# DAC.net
KiCad netlist of a schematic drawn in Altium Designer
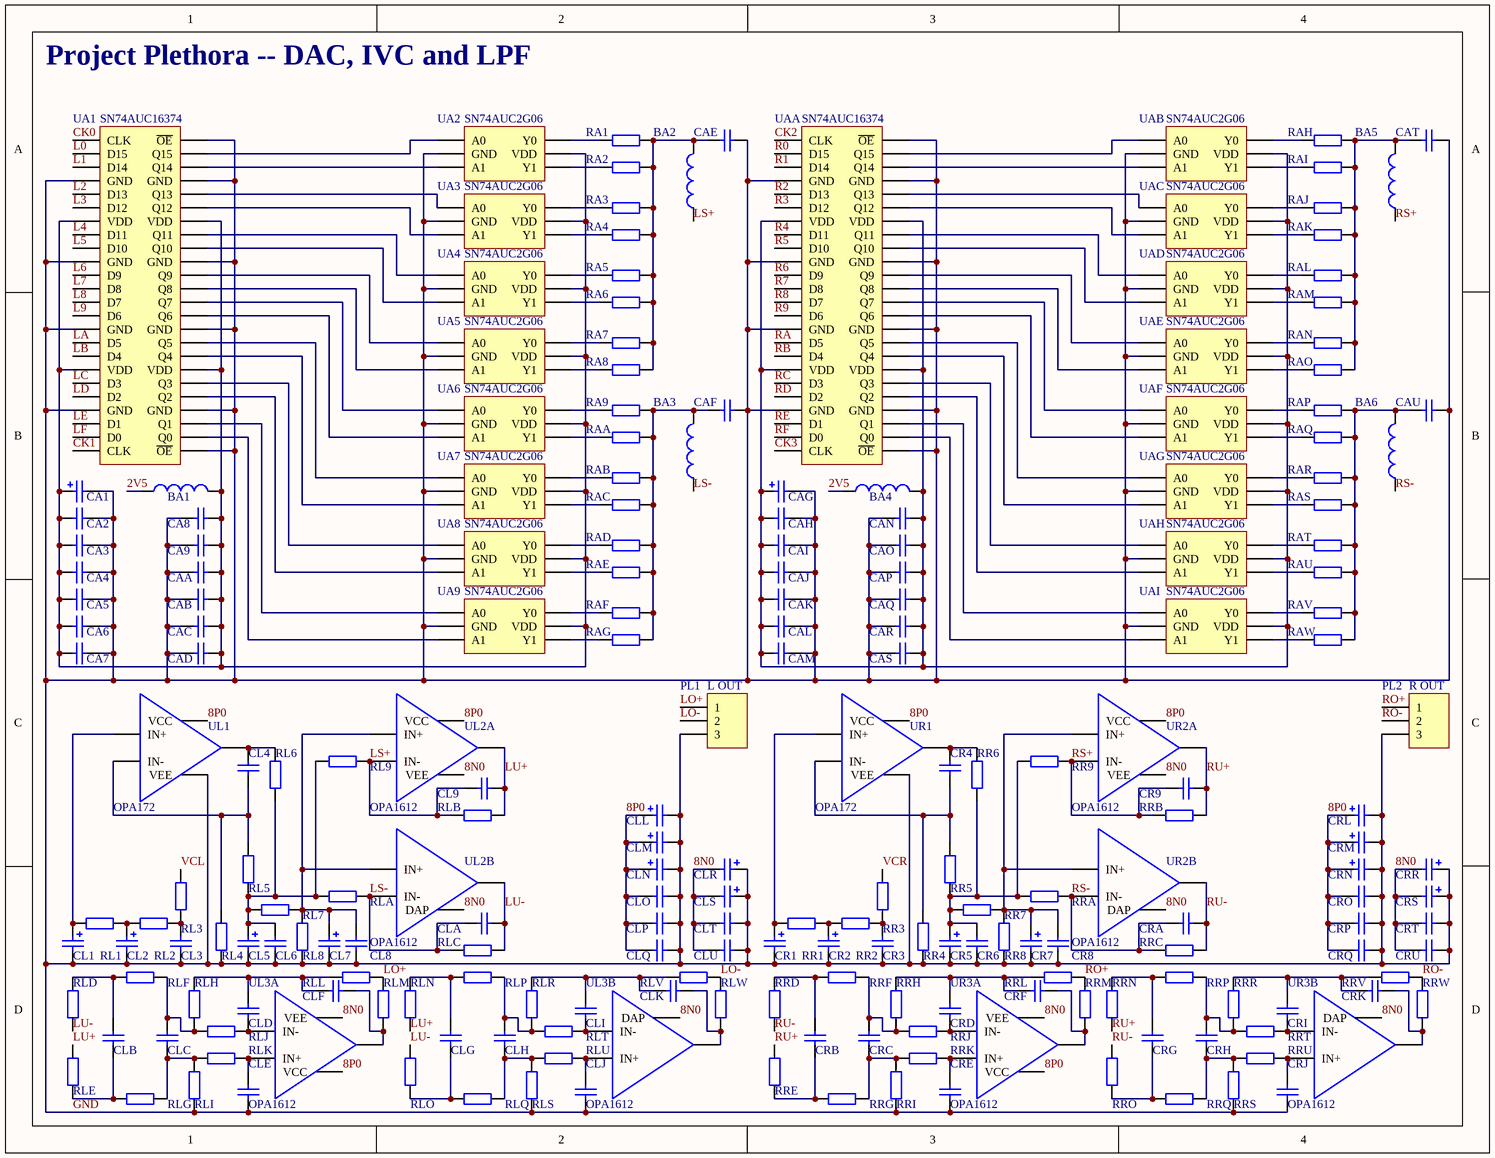
[diagram p0: DAC.SchDoc]

(export (version "E")
  (design (tool "Eeschema 10.0.6"))
  (components
    (comp (ref "BA1")
      (value "Inductor")
      (footprint "0402")
      (fields (field (name "PUBLISHER") "Altium Limited"))
      (libsource (lib "Miscellaneous Devices") (part "Inductor"))
    )
    (comp (ref "BA2")
      (value "Inductor")
      (footprint "0402")
      (fields (field (name "PUBLISHER") "Altium Limited"))
      (libsource (lib "Miscellaneous Devices") (part "Inductor"))
    )
    (comp (ref "BA3")
      (value "Inductor")
      (footprint "0402")
      (fields (field (name "PUBLISHER") "Altium Limited"))
      (libsource (lib "Miscellaneous Devices") (part "Inductor"))
    )
    (comp (ref "BA4")
      (value "Inductor")
      (footprint "0402")
      (fields (field (name "PUBLISHER") "Altium Limited"))
      (libsource (lib "Miscellaneous Devices") (part "Inductor"))
    )
    (comp (ref "BA5")
      (value "Inductor")
      (footprint "0402")
      (fields (field (name "PUBLISHER") "Altium Limited"))
      (libsource (lib "Miscellaneous Devices") (part "Inductor"))
    )
    (comp (ref "BA6")
      (value "Inductor")
      (footprint "0402")
      (fields (field (name "PUBLISHER") "Altium Limited"))
      (libsource (lib "Miscellaneous Devices") (part "Inductor"))
    )
    (comp (ref "CA1")
      (value "Cap Pol2")
      (footprint "0603")
      (description "Polarized Capacitor (Axial)")
      (fields (field (name "PUBLISHER") "Altium Limited"))
      (libsource (lib "Miscellaneous Devices") (part "Cap Pol2"))
    )
    (comp (ref "CA2")
      (value "Cap")
      (footprint "0402")
      (description "Capacitor")
      (fields (field (name "PUBLISHER") "Altium Limited"))
      (libsource (lib "Miscellaneous Devices") (part "Cap"))
    )
    (comp (ref "CA3")
      (value "Cap")
      (footprint "0402")
      (description "Capacitor")
      (fields (field (name "PUBLISHER") "Altium Limited"))
      (libsource (lib "Miscellaneous Devices") (part "Cap"))
    )
    (comp (ref "CA4")
      (value "Cap")
      (footprint "0402")
      (description "Capacitor")
      (fields (field (name "PUBLISHER") "Altium Limited"))
      (libsource (lib "Miscellaneous Devices") (part "Cap"))
    )
    (comp (ref "CA5")
      (value "Cap")
      (footprint "0402")
      (description "Capacitor")
      (fields (field (name "PUBLISHER") "Altium Limited"))
      (libsource (lib "Miscellaneous Devices") (part "Cap"))
    )
    (comp (ref "CA6")
      (value "Cap")
      (footprint "0402")
      (description "Capacitor")
      (fields (field (name "PUBLISHER") "Altium Limited"))
      (libsource (lib "Miscellaneous Devices") (part "Cap"))
    )
    (comp (ref "CA7")
      (value "Cap")
      (footprint "0402")
      (description "Capacitor")
      (fields (field (name "PUBLISHER") "Altium Limited"))
      (libsource (lib "Miscellaneous Devices") (part "Cap"))
    )
    (comp (ref "CA8")
      (value "Cap")
      (footprint "0402")
      (description "Capacitor")
      (fields (field (name "PUBLISHER") "Altium Limited"))
      (libsource (lib "Miscellaneous Devices") (part "Cap"))
    )
    (comp (ref "CA9")
      (value "Cap")
      (footprint "0402")
      (description "Capacitor")
      (fields (field (name "PUBLISHER") "Altium Limited"))
      (libsource (lib "Miscellaneous Devices") (part "Cap"))
    )
    (comp (ref "CAA")
      (value "Cap")
      (footprint "0402")
      (description "Capacitor")
      (fields (field (name "PUBLISHER") "Altium Limited"))
      (libsource (lib "Miscellaneous Devices") (part "Cap"))
    )
    (comp (ref "CAB")
      (value "Cap")
      (footprint "0402")
      (description "Capacitor")
      (fields (field (name "PUBLISHER") "Altium Limited"))
      (libsource (lib "Miscellaneous Devices") (part "Cap"))
    )
    (comp (ref "CAC")
      (value "Cap")
      (footprint "0402")
      (description "Capacitor")
      (fields (field (name "PUBLISHER") "Altium Limited"))
      (libsource (lib "Miscellaneous Devices") (part "Cap"))
    )
    (comp (ref "CAD")
      (value "Cap")
      (footprint "0402")
      (description "Capacitor")
      (fields (field (name "PUBLISHER") "Altium Limited"))
      (libsource (lib "Miscellaneous Devices") (part "Cap"))
    )
    (comp (ref "CAE")
      (value "Cap")
      (footprint "0402")
      (description "Capacitor")
      (fields (field (name "PUBLISHER") "Altium Limited"))
      (libsource (lib "Miscellaneous Devices") (part "Cap"))
    )
    (comp (ref "CAF")
      (value "Cap")
      (footprint "0402")
      (description "Capacitor")
      (fields (field (name "PUBLISHER") "Altium Limited"))
      (libsource (lib "Miscellaneous Devices") (part "Cap"))
    )
    (comp (ref "CAG")
      (value "Cap Pol2")
      (footprint "0603")
      (description "Polarized Capacitor (Axial)")
      (fields (field (name "PUBLISHER") "Altium Limited"))
      (libsource (lib "Miscellaneous Devices") (part "Cap Pol2"))
    )
    (comp (ref "CAH")
      (value "Cap")
      (footprint "0402")
      (description "Capacitor")
      (fields (field (name "PUBLISHER") "Altium Limited"))
      (libsource (lib "Miscellaneous Devices") (part "Cap"))
    )
    (comp (ref "CAI")
      (value "Cap")
      (footprint "0402")
      (description "Capacitor")
      (fields (field (name "PUBLISHER") "Altium Limited"))
      (libsource (lib "Miscellaneous Devices") (part "Cap"))
    )
    (comp (ref "CAJ")
      (value "Cap")
      (footprint "0402")
      (description "Capacitor")
      (fields (field (name "PUBLISHER") "Altium Limited"))
      (libsource (lib "Miscellaneous Devices") (part "Cap"))
    )
    (comp (ref "CAK")
      (value "Cap")
      (footprint "0402")
      (description "Capacitor")
      (fields (field (name "PUBLISHER") "Altium Limited"))
      (libsource (lib "Miscellaneous Devices") (part "Cap"))
    )
    (comp (ref "CAL")
      (value "Cap")
      (footprint "0402")
      (description "Capacitor")
      (fields (field (name "PUBLISHER") "Altium Limited"))
      (libsource (lib "Miscellaneous Devices") (part "Cap"))
    )
    (comp (ref "CAM")
      (value "Cap")
      (footprint "0402")
      (description "Capacitor")
      (fields (field (name "PUBLISHER") "Altium Limited"))
      (libsource (lib "Miscellaneous Devices") (part "Cap"))
    )
    (comp (ref "CAN")
      (value "Cap")
      (footprint "0402")
      (description "Capacitor")
      (fields (field (name "PUBLISHER") "Altium Limited"))
      (libsource (lib "Miscellaneous Devices") (part "Cap"))
    )
    (comp (ref "CAO")
      (value "Cap")
      (footprint "0402")
      (description "Capacitor")
      (fields (field (name "PUBLISHER") "Altium Limited"))
      (libsource (lib "Miscellaneous Devices") (part "Cap"))
    )
    (comp (ref "CAP")
      (value "Cap")
      (footprint "0402")
      (description "Capacitor")
      (fields (field (name "PUBLISHER") "Altium Limited"))
      (libsource (lib "Miscellaneous Devices") (part "Cap"))
    )
    (comp (ref "CAQ")
      (value "Cap")
      (footprint "0402")
      (description "Capacitor")
      (fields (field (name "PUBLISHER") "Altium Limited"))
      (libsource (lib "Miscellaneous Devices") (part "Cap"))
    )
    (comp (ref "CAR")
      (value "Cap")
      (footprint "0402")
      (description "Capacitor")
      (fields (field (name "PUBLISHER") "Altium Limited"))
      (libsource (lib "Miscellaneous Devices") (part "Cap"))
    )
    (comp (ref "CAS")
      (value "Cap")
      (footprint "0402")
      (description "Capacitor")
      (fields (field (name "PUBLISHER") "Altium Limited"))
      (libsource (lib "Miscellaneous Devices") (part "Cap"))
    )
    (comp (ref "CAT")
      (value "Cap")
      (footprint "0402")
      (description "Capacitor")
      (fields (field (name "PUBLISHER") "Altium Limited"))
      (libsource (lib "Miscellaneous Devices") (part "Cap"))
    )
    (comp (ref "CAU")
      (value "Cap")
      (footprint "0402")
      (description "Capacitor")
      (fields (field (name "PUBLISHER") "Altium Limited"))
      (libsource (lib "Miscellaneous Devices") (part "Cap"))
    )
    (comp (ref "CL1")
      (value "Cap Pol2")
      (footprint "0603")
      (description "Polarized Capacitor (Axial)")
      (fields (field (name "PUBLISHER") "Altium Limited"))
      (libsource (lib "Miscellaneous Devices") (part "Cap Pol2"))
    )
    (comp (ref "CL2")
      (value "Cap Pol2")
      (footprint "0603")
      (description "Polarized Capacitor (Axial)")
      (fields (field (name "PUBLISHER") "Altium Limited"))
      (libsource (lib "Miscellaneous Devices") (part "Cap Pol2"))
    )
    (comp (ref "CL3")
      (value "Cap")
      (footprint "0603")
      (description "Capacitor")
      (fields (field (name "PUBLISHER") "Altium Limited"))
      (libsource (lib "Miscellaneous Devices") (part "Cap"))
    )
    (comp (ref "CL4")
      (value "Cap")
      (footprint "0603")
      (description "Capacitor")
      (fields (field (name "PUBLISHER") "Altium Limited"))
      (libsource (lib "Miscellaneous Devices") (part "Cap"))
    )
    (comp (ref "CL5")
      (value "Cap Pol2")
      (footprint "0603")
      (description "Polarized Capacitor (Axial)")
      (fields (field (name "PUBLISHER") "Altium Limited"))
      (libsource (lib "Miscellaneous Devices") (part "Cap Pol2"))
    )
    (comp (ref "CL6")
      (value "Cap")
      (footprint "0603")
      (description "Capacitor")
      (fields (field (name "PUBLISHER") "Altium Limited"))
      (libsource (lib "Miscellaneous Devices") (part "Cap"))
    )
    (comp (ref "CL7")
      (value "Cap Pol2")
      (footprint "0603")
      (description "Polarized Capacitor (Axial)")
      (fields (field (name "PUBLISHER") "Altium Limited"))
      (libsource (lib "Miscellaneous Devices") (part "Cap Pol2"))
    )
    (comp (ref "CL8")
      (value "Cap")
      (footprint "0603")
      (description "Capacitor")
      (fields (field (name "PUBLISHER") "Altium Limited"))
      (libsource (lib "Miscellaneous Devices") (part "Cap"))
    )
    (comp (ref "CL9")
      (value "Cap")
      (footprint "0603")
      (description "Capacitor")
      (fields (field (name "PUBLISHER") "Altium Limited"))
      (libsource (lib "Miscellaneous Devices") (part "Cap"))
    )
    (comp (ref "CLA")
      (value "Cap")
      (footprint "0603")
      (description "Capacitor")
      (fields (field (name "PUBLISHER") "Altium Limited"))
      (libsource (lib "Miscellaneous Devices") (part "Cap"))
    )
    (comp (ref "CLB")
      (value "Cap")
      (footprint "0603")
      (description "Capacitor")
      (fields (field (name "PUBLISHER") "Altium Limited"))
      (libsource (lib "Miscellaneous Devices") (part "Cap"))
    )
    (comp (ref "CLC")
      (value "Cap")
      (footprint "0603")
      (description "Capacitor")
      (fields (field (name "PUBLISHER") "Altium Limited"))
      (libsource (lib "Miscellaneous Devices") (part "Cap"))
    )
    (comp (ref "CLD")
      (value "Cap")
      (footprint "0603")
      (description "Capacitor")
      (fields (field (name "PUBLISHER") "Altium Limited"))
      (libsource (lib "Miscellaneous Devices") (part "Cap"))
    )
    (comp (ref "CLE")
      (value "Cap")
      (footprint "0603")
      (description "Capacitor")
      (fields (field (name "PUBLISHER") "Altium Limited"))
      (libsource (lib "Miscellaneous Devices") (part "Cap"))
    )
    (comp (ref "CLF")
      (value "Cap")
      (footprint "0603")
      (description "Capacitor")
      (fields (field (name "PUBLISHER") "Altium Limited"))
      (libsource (lib "Miscellaneous Devices") (part "Cap"))
    )
    (comp (ref "CLG")
      (value "Cap")
      (footprint "0603")
      (description "Capacitor")
      (fields (field (name "PUBLISHER") "Altium Limited"))
      (libsource (lib "Miscellaneous Devices") (part "Cap"))
    )
    (comp (ref "CLH")
      (value "Cap")
      (footprint "0603")
      (description "Capacitor")
      (fields (field (name "PUBLISHER") "Altium Limited"))
      (libsource (lib "Miscellaneous Devices") (part "Cap"))
    )
    (comp (ref "CLI")
      (value "Cap")
      (footprint "0603")
      (description "Capacitor")
      (fields (field (name "PUBLISHER") "Altium Limited"))
      (libsource (lib "Miscellaneous Devices") (part "Cap"))
    )
    (comp (ref "CLJ")
      (value "Cap")
      (footprint "0603")
      (description "Capacitor")
      (fields (field (name "PUBLISHER") "Altium Limited"))
      (libsource (lib "Miscellaneous Devices") (part "Cap"))
    )
    (comp (ref "CLK")
      (value "Cap")
      (footprint "0603")
      (description "Capacitor")
      (fields (field (name "PUBLISHER") "Altium Limited"))
      (libsource (lib "Miscellaneous Devices") (part "Cap"))
    )
    (comp (ref "CLL")
      (value "Cap Pol2")
      (footprint "0603")
      (description "Polarized Capacitor (Axial)")
      (fields (field (name "PUBLISHER") "Altium Limited"))
      (libsource (lib "Miscellaneous Devices") (part "Cap Pol2"))
    )
    (comp (ref "CLM")
      (value "Cap Pol2")
      (footprint "0603")
      (description "Polarized Capacitor (Axial)")
      (fields (field (name "PUBLISHER") "Altium Limited"))
      (libsource (lib "Miscellaneous Devices") (part "Cap Pol2"))
    )
    (comp (ref "CLN")
      (value "Cap Pol2")
      (footprint "0603")
      (description "Polarized Capacitor (Axial)")
      (fields (field (name "PUBLISHER") "Altium Limited"))
      (libsource (lib "Miscellaneous Devices") (part "Cap Pol2"))
    )
    (comp (ref "CLO")
      (value "Cap")
      (footprint "0603")
      (description "Capacitor")
      (fields (field (name "PUBLISHER") "Altium Limited"))
      (libsource (lib "Miscellaneous Devices") (part "Cap"))
    )
    (comp (ref "CLP")
      (value "Cap")
      (footprint "0603")
      (description "Capacitor")
      (fields (field (name "PUBLISHER") "Altium Limited"))
      (libsource (lib "Miscellaneous Devices") (part "Cap"))
    )
    (comp (ref "CLQ")
      (value "Cap")
      (footprint "0603")
      (description "Capacitor")
      (fields (field (name "PUBLISHER") "Altium Limited"))
      (libsource (lib "Miscellaneous Devices") (part "Cap"))
    )
    (comp (ref "CLR")
      (value "Cap Pol2")
      (footprint "0603")
      (description "Polarized Capacitor (Axial)")
      (fields (field (name "PUBLISHER") "Altium Limited"))
      (libsource (lib "Miscellaneous Devices") (part "Cap Pol2"))
    )
    (comp (ref "CLS")
      (value "Cap Pol2")
      (footprint "0603")
      (description "Polarized Capacitor (Axial)")
      (fields (field (name "PUBLISHER") "Altium Limited"))
      (libsource (lib "Miscellaneous Devices") (part "Cap Pol2"))
    )
    (comp (ref "CLT")
      (value "Cap")
      (footprint "0603")
      (description "Capacitor")
      (fields (field (name "PUBLISHER") "Altium Limited"))
      (libsource (lib "Miscellaneous Devices") (part "Cap"))
    )
    (comp (ref "CLU")
      (value "Cap")
      (footprint "0603")
      (description "Capacitor")
      (fields (field (name "PUBLISHER") "Altium Limited"))
      (libsource (lib "Miscellaneous Devices") (part "Cap"))
    )
    (comp (ref "CR1")
      (value "Cap Pol2")
      (footprint "0603")
      (description "Polarized Capacitor (Axial)")
      (fields (field (name "PUBLISHER") "Altium Limited"))
      (libsource (lib "Miscellaneous Devices") (part "Cap Pol2"))
    )
    (comp (ref "CR2")
      (value "Cap Pol2")
      (footprint "0603")
      (description "Polarized Capacitor (Axial)")
      (fields (field (name "PUBLISHER") "Altium Limited"))
      (libsource (lib "Miscellaneous Devices") (part "Cap Pol2"))
    )
    (comp (ref "CR3")
      (value "Cap")
      (footprint "0603")
      (description "Capacitor")
      (fields (field (name "PUBLISHER") "Altium Limited"))
      (libsource (lib "Miscellaneous Devices") (part "Cap"))
    )
    (comp (ref "CR4")
      (value "Cap")
      (footprint "0603")
      (description "Capacitor")
      (fields (field (name "PUBLISHER") "Altium Limited"))
      (libsource (lib "Miscellaneous Devices") (part "Cap"))
    )
    (comp (ref "CR5")
      (value "Cap Pol2")
      (footprint "0603")
      (description "Polarized Capacitor (Axial)")
      (fields (field (name "PUBLISHER") "Altium Limited"))
      (libsource (lib "Miscellaneous Devices") (part "Cap Pol2"))
    )
    (comp (ref "CR6")
      (value "Cap")
      (footprint "0603")
      (description "Capacitor")
      (fields (field (name "PUBLISHER") "Altium Limited"))
      (libsource (lib "Miscellaneous Devices") (part "Cap"))
    )
    (comp (ref "CR7")
      (value "Cap Pol2")
      (footprint "0603")
      (description "Polarized Capacitor (Axial)")
      (fields (field (name "PUBLISHER") "Altium Limited"))
      (libsource (lib "Miscellaneous Devices") (part "Cap Pol2"))
    )
    (comp (ref "CR8")
      (value "Cap")
      (footprint "0603")
      (description "Capacitor")
      (fields (field (name "PUBLISHER") "Altium Limited"))
      (libsource (lib "Miscellaneous Devices") (part "Cap"))
    )
    (comp (ref "CR9")
      (value "Cap")
      (footprint "0603")
      (description "Capacitor")
      (fields (field (name "PUBLISHER") "Altium Limited"))
      (libsource (lib "Miscellaneous Devices") (part "Cap"))
    )
    (comp (ref "CRA")
      (value "Cap")
      (footprint "0603")
      (description "Capacitor")
      (fields (field (name "PUBLISHER") "Altium Limited"))
      (libsource (lib "Miscellaneous Devices") (part "Cap"))
    )
    (comp (ref "CRB")
      (value "Cap")
      (footprint "0603")
      (description "Capacitor")
      (fields (field (name "PUBLISHER") "Altium Limited"))
      (libsource (lib "Miscellaneous Devices") (part "Cap"))
    )
    (comp (ref "CRC")
      (value "Cap")
      (footprint "0603")
      (description "Capacitor")
      (fields (field (name "PUBLISHER") "Altium Limited"))
      (libsource (lib "Miscellaneous Devices") (part "Cap"))
    )
    (comp (ref "CRD")
      (value "Cap")
      (footprint "0603")
      (description "Capacitor")
      (fields (field (name "PUBLISHER") "Altium Limited"))
      (libsource (lib "Miscellaneous Devices") (part "Cap"))
    )
    (comp (ref "CRE")
      (value "Cap")
      (footprint "0603")
      (description "Capacitor")
      (fields (field (name "PUBLISHER") "Altium Limited"))
      (libsource (lib "Miscellaneous Devices") (part "Cap"))
    )
    (comp (ref "CRF")
      (value "Cap")
      (footprint "0603")
      (description "Capacitor")
      (fields (field (name "PUBLISHER") "Altium Limited"))
      (libsource (lib "Miscellaneous Devices") (part "Cap"))
    )
    (comp (ref "CRG")
      (value "Cap")
      (footprint "0603")
      (description "Capacitor")
      (fields (field (name "PUBLISHER") "Altium Limited"))
      (libsource (lib "Miscellaneous Devices") (part "Cap"))
    )
    (comp (ref "CRH")
      (value "Cap")
      (footprint "0603")
      (description "Capacitor")
      (fields (field (name "PUBLISHER") "Altium Limited"))
      (libsource (lib "Miscellaneous Devices") (part "Cap"))
    )
    (comp (ref "CRI")
      (value "Cap")
      (footprint "0603")
      (description "Capacitor")
      (fields (field (name "PUBLISHER") "Altium Limited"))
      (libsource (lib "Miscellaneous Devices") (part "Cap"))
    )
    (comp (ref "CRJ")
      (value "Cap")
      (footprint "0603")
      (description "Capacitor")
      (fields (field (name "PUBLISHER") "Altium Limited"))
      (libsource (lib "Miscellaneous Devices") (part "Cap"))
    )
    (comp (ref "CRK")
      (value "Cap")
      (footprint "0603")
      (description "Capacitor")
      (fields (field (name "PUBLISHER") "Altium Limited"))
      (libsource (lib "Miscellaneous Devices") (part "Cap"))
    )
    (comp (ref "CRL")
      (value "Cap Pol2")
      (footprint "0603")
      (description "Polarized Capacitor (Axial)")
      (fields (field (name "PUBLISHER") "Altium Limited"))
      (libsource (lib "Miscellaneous Devices") (part "Cap Pol2"))
    )
    (comp (ref "CRM")
      (value "Cap Pol2")
      (footprint "0603")
      (description "Polarized Capacitor (Axial)")
      (fields (field (name "PUBLISHER") "Altium Limited"))
      (libsource (lib "Miscellaneous Devices") (part "Cap Pol2"))
    )
    (comp (ref "CRN")
      (value "Cap Pol2")
      (footprint "0603")
      (description "Polarized Capacitor (Axial)")
      (fields (field (name "PUBLISHER") "Altium Limited"))
      (libsource (lib "Miscellaneous Devices") (part "Cap Pol2"))
    )
    (comp (ref "CRO")
      (value "Cap")
      (footprint "0603")
      (description "Capacitor")
      (fields (field (name "PUBLISHER") "Altium Limited"))
      (libsource (lib "Miscellaneous Devices") (part "Cap"))
    )
    (comp (ref "CRP")
      (value "Cap")
      (footprint "0603")
      (description "Capacitor")
      (fields (field (name "PUBLISHER") "Altium Limited"))
      (libsource (lib "Miscellaneous Devices") (part "Cap"))
    )
    (comp (ref "CRQ")
      (value "Cap")
      (footprint "0603")
      (description "Capacitor")
      (fields (field (name "PUBLISHER") "Altium Limited"))
      (libsource (lib "Miscellaneous Devices") (part "Cap"))
    )
    (comp (ref "CRR")
      (value "Cap Pol2")
      (footprint "0603")
      (description "Polarized Capacitor (Axial)")
      (fields (field (name "PUBLISHER") "Altium Limited"))
      (libsource (lib "Miscellaneous Devices") (part "Cap Pol2"))
    )
    (comp (ref "CRS")
      (value "Cap Pol2")
      (footprint "0603")
      (description "Polarized Capacitor (Axial)")
      (fields (field (name "PUBLISHER") "Altium Limited"))
      (libsource (lib "Miscellaneous Devices") (part "Cap Pol2"))
    )
    (comp (ref "CRT")
      (value "Cap")
      (footprint "0603")
      (description "Capacitor")
      (fields (field (name "PUBLISHER") "Altium Limited"))
      (libsource (lib "Miscellaneous Devices") (part "Cap"))
    )
    (comp (ref "CRU")
      (value "Cap")
      (footprint "0603")
      (description "Capacitor")
      (fields (field (name "PUBLISHER") "Altium Limited"))
      (libsource (lib "Miscellaneous Devices") (part "Cap"))
    )
    (comp (ref "PL1")
      (value "L OUT")
      (footprint "HDR1X3")
      (description "Header, 3-Pin")
      (fields (field (name "PUBLISHER") "Altium Limited"))
      (libsource (lib "Miscellaneous Connectors") (part "Header 3"))
    )
    (comp (ref "PL2")
      (value "R OUT")
      (footprint "HDR1X3")
      (description "Header, 3-Pin")
      (fields (field (name "PUBLISHER") "Altium Limited"))
      (libsource (lib "Miscellaneous Connectors") (part "Header 3"))
    )
    (comp (ref "RA1")
      (value "Res2")
      (footprint "0402")
      (description "Resistor")
      (fields (field (name "PUBLISHER") "Altium Limited"))
      (libsource (lib "") (part "Res2_1"))
    )
    (comp (ref "RA2")
      (value "Res2")
      (footprint "0402")
      (description "Resistor")
      (fields (field (name "PUBLISHER") "Altium Limited"))
      (libsource (lib "") (part "Res2_1"))
    )
    (comp (ref "RA3")
      (value "Res2")
      (footprint "0402")
      (description "Resistor")
      (fields (field (name "PUBLISHER") "Altium Limited"))
      (libsource (lib "") (part "Res2_1"))
    )
    (comp (ref "RA4")
      (value "Res2")
      (footprint "0402")
      (description "Resistor")
      (fields (field (name "PUBLISHER") "Altium Limited"))
      (libsource (lib "") (part "Res2_1"))
    )
    (comp (ref "RA5")
      (value "Res2")
      (footprint "0402")
      (description "Resistor")
      (fields (field (name "PUBLISHER") "Altium Limited"))
      (libsource (lib "") (part "Res2_1"))
    )
    (comp (ref "RA6")
      (value "Res2")
      (footprint "0402")
      (description "Resistor")
      (fields (field (name "PUBLISHER") "Altium Limited"))
      (libsource (lib "") (part "Res2_1"))
    )
    (comp (ref "RA7")
      (value "Res2")
      (footprint "0402")
      (description "Resistor")
      (fields (field (name "PUBLISHER") "Altium Limited"))
      (libsource (lib "") (part "Res2_1"))
    )
    (comp (ref "RA8")
      (value "Res2")
      (footprint "0402")
      (description "Resistor")
      (fields (field (name "PUBLISHER") "Altium Limited"))
      (libsource (lib "") (part "Res2_1"))
    )
    (comp (ref "RA9")
      (value "Res2")
      (footprint "0402")
      (description "Resistor")
      (fields (field (name "PUBLISHER") "Altium Limited"))
      (libsource (lib "") (part "Res2_1"))
    )
    (comp (ref "RAA")
      (value "Res2")
      (footprint "0402")
      (description "Resistor")
      (fields (field (name "PUBLISHER") "Altium Limited"))
      (libsource (lib "") (part "Res2_1"))
    )
    (comp (ref "RAB")
      (value "Res2")
      (footprint "0402")
      (description "Resistor")
      (fields (field (name "PUBLISHER") "Altium Limited"))
      (libsource (lib "") (part "Res2_1"))
    )
    (comp (ref "RAC")
      (value "Res2")
      (footprint "0402")
      (description "Resistor")
      (fields (field (name "PUBLISHER") "Altium Limited"))
      (libsource (lib "") (part "Res2_1"))
    )
    (comp (ref "RAD")
      (value "Res2")
      (footprint "0402")
      (description "Resistor")
      (fields (field (name "PUBLISHER") "Altium Limited"))
      (libsource (lib "") (part "Res2_1"))
    )
    (comp (ref "RAE")
      (value "Res2")
      (footprint "0402")
      (description "Resistor")
      (fields (field (name "PUBLISHER") "Altium Limited"))
      (libsource (lib "") (part "Res2_1"))
    )
    (comp (ref "RAF")
      (value "Res2")
      (footprint "0402")
      (description "Resistor")
      (fields (field (name "PUBLISHER") "Altium Limited"))
      (libsource (lib "") (part "Res2_1"))
    )
    (comp (ref "RAG")
      (value "Res2")
      (footprint "0402")
      (description "Resistor")
      (fields (field (name "PUBLISHER") "Altium Limited"))
      (libsource (lib "") (part "Res2_1"))
    )
    (comp (ref "RAH")
      (value "Res2")
      (footprint "0402")
      (description "Resistor")
      (fields (field (name "PUBLISHER") "Altium Limited"))
      (libsource (lib "") (part "Res2_1"))
    )
    (comp (ref "RAI")
      (value "Res2")
      (footprint "0402")
      (description "Resistor")
      (fields (field (name "PUBLISHER") "Altium Limited"))
      (libsource (lib "") (part "Res2_1"))
    )
    (comp (ref "RAJ")
      (value "Res2")
      (footprint "0402")
      (description "Resistor")
      (fields (field (name "PUBLISHER") "Altium Limited"))
      (libsource (lib "") (part "Res2_1"))
    )
    (comp (ref "RAK")
      (value "Res2")
      (footprint "0402")
      (description "Resistor")
      (fields (field (name "PUBLISHER") "Altium Limited"))
      (libsource (lib "") (part "Res2_1"))
    )
    (comp (ref "RAL")
      (value "Res2")
      (footprint "0402")
      (description "Resistor")
      (fields (field (name "PUBLISHER") "Altium Limited"))
      (libsource (lib "") (part "Res2_1"))
    )
    (comp (ref "RAM")
      (value "Res2")
      (footprint "0402")
      (description "Resistor")
      (fields (field (name "PUBLISHER") "Altium Limited"))
      (libsource (lib "") (part "Res2_1"))
    )
    (comp (ref "RAN")
      (value "Res2")
      (footprint "0402")
      (description "Resistor")
      (fields (field (name "PUBLISHER") "Altium Limited"))
      (libsource (lib "") (part "Res2_1"))
    )
    (comp (ref "RAO")
      (value "Res2")
      (footprint "0402")
      (description "Resistor")
      (fields (field (name "PUBLISHER") "Altium Limited"))
      (libsource (lib "") (part "Res2_1"))
    )
    (comp (ref "RAP")
      (value "Res2")
      (footprint "0402")
      (description "Resistor")
      (fields (field (name "PUBLISHER") "Altium Limited"))
      (libsource (lib "") (part "Res2_1"))
    )
    (comp (ref "RAQ")
      (value "Res2")
      (footprint "0402")
      (description "Resistor")
      (fields (field (name "PUBLISHER") "Altium Limited"))
      (libsource (lib "") (part "Res2_1"))
    )
    (comp (ref "RAR")
      (value "Res2")
      (footprint "0402")
      (description "Resistor")
      (fields (field (name "PUBLISHER") "Altium Limited"))
      (libsource (lib "") (part "Res2_1"))
    )
    (comp (ref "RAS")
      (value "Res2")
      (footprint "0402")
      (description "Resistor")
      (fields (field (name "PUBLISHER") "Altium Limited"))
      (libsource (lib "") (part "Res2_1"))
    )
    (comp (ref "RAT")
      (value "Res2")
      (footprint "0402")
      (description "Resistor")
      (fields (field (name "PUBLISHER") "Altium Limited"))
      (libsource (lib "") (part "Res2_1"))
    )
    (comp (ref "RAU")
      (value "Res2")
      (footprint "0402")
      (description "Resistor")
      (fields (field (name "PUBLISHER") "Altium Limited"))
      (libsource (lib "") (part "Res2_1"))
    )
    (comp (ref "RAV")
      (value "Res2")
      (footprint "0402")
      (description "Resistor")
      (fields (field (name "PUBLISHER") "Altium Limited"))
      (libsource (lib "") (part "Res2_1"))
    )
    (comp (ref "RAW")
      (value "Res2")
      (footprint "0402")
      (description "Resistor")
      (fields (field (name "PUBLISHER") "Altium Limited"))
      (libsource (lib "") (part "Res2_1"))
    )
    (comp (ref "RL1")
      (value "Res2")
      (footprint "0402")
      (description "Resistor")
      (fields (field (name "PUBLISHER") "Altium Limited"))
      (libsource (lib "") (part "Res2_1"))
    )
    (comp (ref "RL2")
      (value "Res2")
      (footprint "0402")
      (description "Resistor")
      (fields (field (name "PUBLISHER") "Altium Limited"))
      (libsource (lib "") (part "Res2_2"))
    )
    (comp (ref "RL3")
      (value "Res2")
      (footprint "0402")
      (description "Resistor")
      (fields (field (name "PUBLISHER") "Altium Limited"))
      (libsource (lib "Miscellaneous Devices") (part "Res2"))
    )
    (comp (ref "RL4")
      (value "Res2")
      (footprint "0402")
      (description "Resistor")
      (fields (field (name "PUBLISHER") "Altium Limited"))
      (libsource (lib "Miscellaneous Devices") (part "Res2"))
    )
    (comp (ref "RL5")
      (value "Res2")
      (footprint "0402")
      (description "Resistor")
      (fields (field (name "PUBLISHER") "Altium Limited"))
      (libsource (lib "Miscellaneous Devices") (part "Res2"))
    )
    (comp (ref "RL6")
      (value "Res2")
      (footprint "0402")
      (description "Resistor")
      (fields (field (name "PUBLISHER") "Altium Limited"))
      (libsource (lib "Miscellaneous Devices") (part "Res2"))
    )
    (comp (ref "RL7")
      (value "Res2")
      (footprint "0402")
      (description "Resistor")
      (fields (field (name "PUBLISHER") "Altium Limited"))
      (libsource (lib "") (part "Res2_2"))
    )
    (comp (ref "RL8")
      (value "Res2")
      (footprint "0402")
      (description "Resistor")
      (fields (field (name "PUBLISHER") "Altium Limited"))
      (libsource (lib "Miscellaneous Devices") (part "Res2"))
    )
    (comp (ref "RL9")
      (value "Res2")
      (footprint "0402")
      (description "Resistor")
      (fields (field (name "PUBLISHER") "Altium Limited"))
      (libsource (lib "") (part "Res2_1"))
    )
    (comp (ref "RLA")
      (value "Res2")
      (footprint "0402")
      (description "Resistor")
      (fields (field (name "PUBLISHER") "Altium Limited"))
      (libsource (lib "") (part "Res2_1"))
    )
    (comp (ref "RLB")
      (value "Res2")
      (footprint "0402")
      (description "Resistor")
      (fields (field (name "PUBLISHER") "Altium Limited"))
      (libsource (lib "") (part "Res2_1"))
    )
    (comp (ref "RLC")
      (value "Res2")
      (footprint "0402")
      (description "Resistor")
      (fields (field (name "PUBLISHER") "Altium Limited"))
      (libsource (lib "") (part "Res2_1"))
    )
    (comp (ref "RLD")
      (value "Res2")
      (footprint "0402")
      (description "Resistor")
      (fields (field (name "PUBLISHER") "Altium Limited"))
      (libsource (lib "Miscellaneous Devices") (part "Res2"))
    )
    (comp (ref "RLE")
      (value "Res2")
      (footprint "0402")
      (description "Resistor")
      (fields (field (name "PUBLISHER") "Altium Limited"))
      (libsource (lib "Miscellaneous Devices") (part "Res2"))
    )
    (comp (ref "RLF")
      (value "Res2")
      (footprint "0402")
      (description "Resistor")
      (fields (field (name "PUBLISHER") "Altium Limited"))
      (libsource (lib "") (part "Res2_2"))
    )
    (comp (ref "RLG")
      (value "Res2")
      (footprint "0402")
      (description "Resistor")
      (fields (field (name "PUBLISHER") "Altium Limited"))
      (libsource (lib "") (part "Res2_2"))
    )
    (comp (ref "RLH")
      (value "Res2")
      (footprint "0402")
      (description "Resistor")
      (fields (field (name "PUBLISHER") "Altium Limited"))
      (libsource (lib "") (part "Res2_1"))
    )
    (comp (ref "RLI")
      (value "Res2")
      (footprint "0402")
      (description "Resistor")
      (fields (field (name "PUBLISHER") "Altium Limited"))
      (libsource (lib "") (part "Res2_1"))
    )
    (comp (ref "RLJ")
      (value "Res2")
      (footprint "0402")
      (description "Resistor")
      (fields (field (name "PUBLISHER") "Altium Limited"))
      (libsource (lib "") (part "Res2_3"))
    )
    (comp (ref "RLK")
      (value "Res2")
      (footprint "0402")
      (description "Resistor")
      (fields (field (name "PUBLISHER") "Altium Limited"))
      (libsource (lib "") (part "Res2_3"))
    )
    (comp (ref "RLL")
      (value "Res2")
      (footprint "0402")
      (description "Resistor")
      (fields (field (name "PUBLISHER") "Altium Limited"))
      (libsource (lib "Miscellaneous Devices") (part "Res2"))
    )
    (comp (ref "RLM")
      (value "Res2")
      (footprint "0402")
      (description "Resistor")
      (fields (field (name "PUBLISHER") "Altium Limited"))
      (libsource (lib "") (part "Res2_2"))
    )
    (comp (ref "RLN")
      (value "Res2")
      (footprint "0402")
      (description "Resistor")
      (fields (field (name "PUBLISHER") "Altium Limited"))
      (libsource (lib "Miscellaneous Devices") (part "Res2"))
    )
    (comp (ref "RLO")
      (value "Res2")
      (footprint "0402")
      (description "Resistor")
      (fields (field (name "PUBLISHER") "Altium Limited"))
      (libsource (lib "Miscellaneous Devices") (part "Res2"))
    )
    (comp (ref "RLP")
      (value "Res2")
      (footprint "0402")
      (description "Resistor")
      (fields (field (name "PUBLISHER") "Altium Limited"))
      (libsource (lib "") (part "Res2_2"))
    )
    (comp (ref "RLQ")
      (value "Res2")
      (footprint "0402")
      (description "Resistor")
      (fields (field (name "PUBLISHER") "Altium Limited"))
      (libsource (lib "") (part "Res2_2"))
    )
    (comp (ref "RLR")
      (value "Res2")
      (footprint "0402")
      (description "Resistor")
      (fields (field (name "PUBLISHER") "Altium Limited"))
      (libsource (lib "") (part "Res2_1"))
    )
    (comp (ref "RLS")
      (value "Res2")
      (footprint "0402")
      (description "Resistor")
      (fields (field (name "PUBLISHER") "Altium Limited"))
      (libsource (lib "") (part "Res2_1"))
    )
    (comp (ref "RLT")
      (value "Res2")
      (footprint "0402")
      (description "Resistor")
      (fields (field (name "PUBLISHER") "Altium Limited"))
      (libsource (lib "") (part "Res2_3"))
    )
    (comp (ref "RLU")
      (value "Res2")
      (footprint "0402")
      (description "Resistor")
      (fields (field (name "PUBLISHER") "Altium Limited"))
      (libsource (lib "") (part "Res2_3"))
    )
    (comp (ref "RLV")
      (value "Res2")
      (footprint "0402")
      (description "Resistor")
      (fields (field (name "PUBLISHER") "Altium Limited"))
      (libsource (lib "Miscellaneous Devices") (part "Res2"))
    )
    (comp (ref "RLW")
      (value "Res2")
      (footprint "0402")
      (description "Resistor")
      (fields (field (name "PUBLISHER") "Altium Limited"))
      (libsource (lib "") (part "Res2_2"))
    )
    (comp (ref "RR1")
      (value "Res2")
      (footprint "0402")
      (description "Resistor")
      (fields (field (name "PUBLISHER") "Altium Limited"))
      (libsource (lib "") (part "Res2_1"))
    )
    (comp (ref "RR2")
      (value "Res2")
      (footprint "0402")
      (description "Resistor")
      (fields (field (name "PUBLISHER") "Altium Limited"))
      (libsource (lib "") (part "Res2_2"))
    )
    (comp (ref "RR3")
      (value "Res2")
      (footprint "0402")
      (description "Resistor")
      (fields (field (name "PUBLISHER") "Altium Limited"))
      (libsource (lib "Miscellaneous Devices") (part "Res2"))
    )
    (comp (ref "RR4")
      (value "Res2")
      (footprint "0402")
      (description "Resistor")
      (fields (field (name "PUBLISHER") "Altium Limited"))
      (libsource (lib "Miscellaneous Devices") (part "Res2"))
    )
    (comp (ref "RR5")
      (value "Res2")
      (footprint "0402")
      (description "Resistor")
      (fields (field (name "PUBLISHER") "Altium Limited"))
      (libsource (lib "Miscellaneous Devices") (part "Res2"))
    )
    (comp (ref "RR6")
      (value "Res2")
      (footprint "0402")
      (description "Resistor")
      (fields (field (name "PUBLISHER") "Altium Limited"))
      (libsource (lib "Miscellaneous Devices") (part "Res2"))
    )
    (comp (ref "RR7")
      (value "Res2")
      (footprint "0402")
      (description "Resistor")
      (fields (field (name "PUBLISHER") "Altium Limited"))
      (libsource (lib "") (part "Res2_2"))
    )
    (comp (ref "RR8")
      (value "Res2")
      (footprint "0402")
      (description "Resistor")
      (fields (field (name "PUBLISHER") "Altium Limited"))
      (libsource (lib "Miscellaneous Devices") (part "Res2"))
    )
    (comp (ref "RR9")
      (value "Res2")
      (footprint "0402")
      (description "Resistor")
      (fields (field (name "PUBLISHER") "Altium Limited"))
      (libsource (lib "") (part "Res2_1"))
    )
    (comp (ref "RRA")
      (value "Res2")
      (footprint "0402")
      (description "Resistor")
      (fields (field (name "PUBLISHER") "Altium Limited"))
      (libsource (lib "") (part "Res2_1"))
    )
    (comp (ref "RRB")
      (value "Res2")
      (footprint "0402")
      (description "Resistor")
      (fields (field (name "PUBLISHER") "Altium Limited"))
      (libsource (lib "") (part "Res2_1"))
    )
    (comp (ref "RRC")
      (value "Res2")
      (footprint "0402")
      (description "Resistor")
      (fields (field (name "PUBLISHER") "Altium Limited"))
      (libsource (lib "") (part "Res2_1"))
    )
    (comp (ref "RRD")
      (value "Res2")
      (footprint "0402")
      (description "Resistor")
      (fields (field (name "PUBLISHER") "Altium Limited"))
      (libsource (lib "Miscellaneous Devices") (part "Res2"))
    )
    (comp (ref "RRE")
      (value "Res2")
      (footprint "0402")
      (description "Resistor")
      (fields (field (name "PUBLISHER") "Altium Limited"))
      (libsource (lib "Miscellaneous Devices") (part "Res2"))
    )
    (comp (ref "RRF")
      (value "Res2")
      (footprint "0402")
      (description "Resistor")
      (fields (field (name "PUBLISHER") "Altium Limited"))
      (libsource (lib "") (part "Res2_2"))
    )
    (comp (ref "RRG")
      (value "Res2")
      (footprint "0402")
      (description "Resistor")
      (fields (field (name "PUBLISHER") "Altium Limited"))
      (libsource (lib "") (part "Res2_2"))
    )
    (comp (ref "RRH")
      (value "Res2")
      (footprint "0402")
      (description "Resistor")
      (fields (field (name "PUBLISHER") "Altium Limited"))
      (libsource (lib "") (part "Res2_1"))
    )
    (comp (ref "RRI")
      (value "Res2")
      (footprint "0402")
      (description "Resistor")
      (fields (field (name "PUBLISHER") "Altium Limited"))
      (libsource (lib "") (part "Res2_1"))
    )
    (comp (ref "RRJ")
      (value "Res2")
      (footprint "0402")
      (description "Resistor")
      (fields (field (name "PUBLISHER") "Altium Limited"))
      (libsource (lib "") (part "Res2_3"))
    )
    (comp (ref "RRK")
      (value "Res2")
      (footprint "0402")
      (description "Resistor")
      (fields (field (name "PUBLISHER") "Altium Limited"))
      (libsource (lib "") (part "Res2_3"))
    )
    (comp (ref "RRL")
      (value "Res2")
      (footprint "0402")
      (description "Resistor")
      (fields (field (name "PUBLISHER") "Altium Limited"))
      (libsource (lib "Miscellaneous Devices") (part "Res2"))
    )
    (comp (ref "RRM")
      (value "Res2")
      (footprint "0402")
      (description "Resistor")
      (fields (field (name "PUBLISHER") "Altium Limited"))
      (libsource (lib "") (part "Res2_2"))
    )
    (comp (ref "RRN")
      (value "Res2")
      (footprint "0402")
      (description "Resistor")
      (fields (field (name "PUBLISHER") "Altium Limited"))
      (libsource (lib "Miscellaneous Devices") (part "Res2"))
    )
    (comp (ref "RRO")
      (value "Res2")
      (footprint "0402")
      (description "Resistor")
      (fields (field (name "PUBLISHER") "Altium Limited"))
      (libsource (lib "Miscellaneous Devices") (part "Res2"))
    )
    (comp (ref "RRP")
      (value "Res2")
      (footprint "0402")
      (description "Resistor")
      (fields (field (name "PUBLISHER") "Altium Limited"))
      (libsource (lib "") (part "Res2_2"))
    )
    (comp (ref "RRQ")
      (value "Res2")
      (footprint "0402")
      (description "Resistor")
      (fields (field (name "PUBLISHER") "Altium Limited"))
      (libsource (lib "") (part "Res2_2"))
    )
    (comp (ref "RRR")
      (value "Res2")
      (footprint "0402")
      (description "Resistor")
      (fields (field (name "PUBLISHER") "Altium Limited"))
      (libsource (lib "") (part "Res2_1"))
    )
    (comp (ref "RRS")
      (value "Res2")
      (footprint "0402")
      (description "Resistor")
      (fields (field (name "PUBLISHER") "Altium Limited"))
      (libsource (lib "") (part "Res2_1"))
    )
    (comp (ref "RRT")
      (value "Res2")
      (footprint "0402")
      (description "Resistor")
      (fields (field (name "PUBLISHER") "Altium Limited"))
      (libsource (lib "") (part "Res2_3"))
    )
    (comp (ref "RRU")
      (value "Res2")
      (footprint "0402")
      (description "Resistor")
      (fields (field (name "PUBLISHER") "Altium Limited"))
      (libsource (lib "") (part "Res2_3"))
    )
    (comp (ref "RRV")
      (value "Res2")
      (footprint "0402")
      (description "Resistor")
      (fields (field (name "PUBLISHER") "Altium Limited"))
      (libsource (lib "Miscellaneous Devices") (part "Res2"))
    )
    (comp (ref "RRW")
      (value "Res2")
      (footprint "0402")
      (description "Resistor")
      (fields (field (name "PUBLISHER") "Altium Limited"))
      (libsource (lib "") (part "Res2_2"))
    )
    (comp (ref "UA1")
      (value "SN74AUC16374")
      (footprint "TSSOP48")
      (libsource (lib "UDAC") (part "SN74AUC16374"))
    )
    (comp (ref "UA2") (value "SN74AUC2G06") (footprint "SC706") (libsource (lib "UDAC") (part "SN74AUC2G06")))
    (comp (ref "UA3") (value "SN74AUC2G06") (footprint "SC706") (libsource (lib "UDAC") (part "SN74AUC2G06")))
    (comp (ref "UA4") (value "SN74AUC2G06") (footprint "SC706") (libsource (lib "UDAC") (part "SN74AUC2G06")))
    (comp (ref "UA5") (value "SN74AUC2G06") (footprint "SC706") (libsource (lib "UDAC") (part "SN74AUC2G06")))
    (comp (ref "UA6") (value "SN74AUC2G06") (footprint "SC706") (libsource (lib "UDAC") (part "SN74AUC2G06")))
    (comp (ref "UA7") (value "SN74AUC2G06") (footprint "SC706") (libsource (lib "UDAC") (part "SN74AUC2G06")))
    (comp (ref "UA8") (value "SN74AUC2G06") (footprint "SC706") (libsource (lib "UDAC") (part "SN74AUC2G06")))
    (comp (ref "UA9") (value "SN74AUC2G06") (footprint "SC706") (libsource (lib "UDAC") (part "SN74AUC2G06")))
    (comp (ref "UAA")
      (value "SN74AUC16374")
      (footprint "TSSOP48")
      (libsource (lib "UDAC") (part "SN74AUC16374"))
    )
    (comp (ref "UAB") (value "SN74AUC2G06") (footprint "SC706") (libsource (lib "UDAC") (part "SN74AUC2G06")))
    (comp (ref "UAC") (value "SN74AUC2G06") (footprint "SC706") (libsource (lib "UDAC") (part "SN74AUC2G06")))
    (comp (ref "UAD") (value "SN74AUC2G06") (footprint "SC706") (libsource (lib "UDAC") (part "SN74AUC2G06")))
    (comp (ref "UAE") (value "SN74AUC2G06") (footprint "SC706") (libsource (lib "UDAC") (part "SN74AUC2G06")))
    (comp (ref "UAF") (value "SN74AUC2G06") (footprint "SC706") (libsource (lib "UDAC") (part "SN74AUC2G06")))
    (comp (ref "UAG") (value "SN74AUC2G06") (footprint "SC706") (libsource (lib "UDAC") (part "SN74AUC2G06")))
    (comp (ref "UAH") (value "SN74AUC2G06") (footprint "SC706") (libsource (lib "UDAC") (part "SN74AUC2G06")))
    (comp (ref "UAI") (value "SN74AUC2G06") (footprint "SC706") (libsource (lib "UDAC") (part "SN74AUC2G06")))
    (comp (ref "UL1") (value "OPA172") (footprint "SC705") (libsource (lib "UDAC") (part "OPA172")))
    (comp (ref "UL2") (value "OPA1612") (footprint "DFN8") (libsource (lib "UDAC") (part "OPA1612")))
    (comp (ref "UL3") (value "OPA1612") (footprint "DFN8") (libsource (lib "UDAC") (part "OPA1612")))
    (comp (ref "UR1") (value "OPA172") (footprint "SC705") (libsource (lib "UDAC") (part "OPA172")))
    (comp (ref "UR2") (value "OPA1612") (footprint "DFN8") (libsource (lib "UDAC") (part "OPA1612")))
    (comp (ref "UR3") (value "OPA1612") (footprint "DFN8") (libsource (lib "UDAC") (part "OPA1612")))
  )
  (nets
    (net (code "1") (name "/2V5") (class "Default")
      (node (ref "BA1") (pin "1") (pinfunction "1_1") (pintype "passive"))
      (node (ref "BA4") (pin "1") (pinfunction "1_1") (pintype "passive"))
    )
    (net (code "2") (name "/8N0") (class "Default")
      (node (ref "CLR") (pin "2") (pinfunction "2_2") (pintype "passive"))
      (node (ref "CLS") (pin "2") (pinfunction "2_2") (pintype "passive"))
      (node (ref "CLT") (pin "1") (pinfunction "1_1") (pintype "passive"))
      (node (ref "CLU") (pin "1") (pinfunction "1_1") (pintype "passive"))
      (node (ref "CRR") (pin "2") (pinfunction "2_2") (pintype "passive"))
      (node (ref "CRS") (pin "2") (pinfunction "2_2") (pintype "passive"))
      (node (ref "CRT") (pin "1") (pinfunction "1_1") (pintype "passive"))
      (node (ref "CRU") (pin "1") (pinfunction "1_1") (pintype "passive"))
      (node (ref "UL2") (pin "4") (pinfunction "VEE_4") (pintype "passive"))
      (node (ref "UL2") (pin "9") (pinfunction "DAP_9") (pintype "passive"))
      (node (ref "UL3") (pin "4") (pinfunction "VEE_4") (pintype "passive"))
      (node (ref "UL3") (pin "9") (pinfunction "DAP_9") (pintype "passive"))
      (node (ref "UR2") (pin "4") (pinfunction "VEE_4") (pintype "passive"))
      (node (ref "UR2") (pin "9") (pinfunction "DAP_9") (pintype "passive"))
      (node (ref "UR3") (pin "4") (pinfunction "VEE_4") (pintype "passive"))
      (node (ref "UR3") (pin "9") (pinfunction "DAP_9") (pintype "passive"))
    )
    (net (code "3") (name "/8P0") (class "Default")
      (node (ref "CLL") (pin "1") (pinfunction "1_1") (pintype "passive"))
      (node (ref "CLM") (pin "1") (pinfunction "1_1") (pintype "passive"))
      (node (ref "CLN") (pin "1") (pinfunction "1_1") (pintype "passive"))
      (node (ref "CLO") (pin "2") (pinfunction "2_2") (pintype "passive"))
      (node (ref "CLP") (pin "2") (pinfunction "2_2") (pintype "passive"))
      (node (ref "CLQ") (pin "2") (pinfunction "2_2") (pintype "passive"))
      (node (ref "CRL") (pin "1") (pinfunction "1_1") (pintype "passive"))
      (node (ref "CRM") (pin "1") (pinfunction "1_1") (pintype "passive"))
      (node (ref "CRN") (pin "1") (pinfunction "1_1") (pintype "passive"))
      (node (ref "CRO") (pin "2") (pinfunction "2_2") (pintype "passive"))
      (node (ref "CRP") (pin "2") (pinfunction "2_2") (pintype "passive"))
      (node (ref "CRQ") (pin "2") (pinfunction "2_2") (pintype "passive"))
      (node (ref "UL1") (pin "5") (pinfunction "VCC_5") (pintype "passive"))
      (node (ref "UL2") (pin "8") (pinfunction "VCC_8") (pintype "passive"))
      (node (ref "UL3") (pin "8") (pinfunction "VCC_8") (pintype "passive"))
      (node (ref "UR1") (pin "5") (pinfunction "VCC_5") (pintype "passive"))
      (node (ref "UR2") (pin "8") (pinfunction "VCC_8") (pintype "passive"))
      (node (ref "UR3") (pin "8") (pinfunction "VCC_8") (pintype "passive"))
    )
    (net (code "4") (name "/CK0") (class "Default")
      (node (ref "UA1") (pin "25") (pinfunction "CLK_25") (pintype "passive"))
    )
    (net (code "5") (name "/CK1") (class "Default")
      (node (ref "UA1") (pin "48") (pinfunction "CLK_48") (pintype "passive"))
    )
    (net (code "6") (name "/CK2") (class "Default")
      (node (ref "UAA") (pin "25") (pinfunction "CLK_25") (pintype "passive"))
    )
    (net (code "7") (name "/CK3") (class "Default")
      (node (ref "UAA") (pin "48") (pinfunction "CLK_48") (pintype "passive"))
    )
    (net (code "8") (name "/GND") (class "Default")
      (node (ref "CA1") (pin "2") (pinfunction "2_2") (pintype "passive"))
      (node (ref "CA2") (pin "2") (pinfunction "2_2") (pintype "passive"))
      (node (ref "CA3") (pin "2") (pinfunction "2_2") (pintype "passive"))
      (node (ref "CA4") (pin "2") (pinfunction "2_2") (pintype "passive"))
      (node (ref "CA5") (pin "2") (pinfunction "2_2") (pintype "passive"))
      (node (ref "CA6") (pin "2") (pinfunction "2_2") (pintype "passive"))
      (node (ref "CA7") (pin "2") (pinfunction "2_2") (pintype "passive"))
      (node (ref "CA8") (pin "1") (pinfunction "1_1") (pintype "passive"))
      (node (ref "CA9") (pin "1") (pinfunction "1_1") (pintype "passive"))
      (node (ref "CAA") (pin "1") (pinfunction "1_1") (pintype "passive"))
      (node (ref "CAB") (pin "1") (pinfunction "1_1") (pintype "passive"))
      (node (ref "CAC") (pin "1") (pinfunction "1_1") (pintype "passive"))
      (node (ref "CAD") (pin "1") (pinfunction "1_1") (pintype "passive"))
      (node (ref "CAE") (pin "1") (pinfunction "1_1") (pintype "passive"))
      (node (ref "CAF") (pin "1") (pinfunction "1_1") (pintype "passive"))
      (node (ref "CAG") (pin "2") (pinfunction "2_2") (pintype "passive"))
      (node (ref "CAH") (pin "2") (pinfunction "2_2") (pintype "passive"))
      (node (ref "CAI") (pin "2") (pinfunction "2_2") (pintype "passive"))
      (node (ref "CAJ") (pin "2") (pinfunction "2_2") (pintype "passive"))
      (node (ref "CAK") (pin "2") (pinfunction "2_2") (pintype "passive"))
      (node (ref "CAL") (pin "2") (pinfunction "2_2") (pintype "passive"))
      (node (ref "CAM") (pin "2") (pinfunction "2_2") (pintype "passive"))
      (node (ref "CAN") (pin "1") (pinfunction "1_1") (pintype "passive"))
      (node (ref "CAO") (pin "1") (pinfunction "1_1") (pintype "passive"))
      (node (ref "CAP") (pin "1") (pinfunction "1_1") (pintype "passive"))
      (node (ref "CAQ") (pin "1") (pinfunction "1_1") (pintype "passive"))
      (node (ref "CAR") (pin "1") (pinfunction "1_1") (pintype "passive"))
      (node (ref "CAS") (pin "1") (pinfunction "1_1") (pintype "passive"))
      (node (ref "CAT") (pin "1") (pinfunction "1_1") (pintype "passive"))
      (node (ref "CAU") (pin "1") (pinfunction "1_1") (pintype "passive"))
      (node (ref "CL1") (pin "2") (pinfunction "2_2") (pintype "passive"))
      (node (ref "CL2") (pin "2") (pinfunction "2_2") (pintype "passive"))
      (node (ref "CL3") (pin "1") (pinfunction "1_1") (pintype "passive"))
      (node (ref "CL5") (pin "2") (pinfunction "2_2") (pintype "passive"))
      (node (ref "CL6") (pin "1") (pinfunction "1_1") (pintype "passive"))
      (node (ref "CL7") (pin "2") (pinfunction "2_2") (pintype "passive"))
      (node (ref "CL8") (pin "1") (pinfunction "1_1") (pintype "passive"))
      (node (ref "CLE") (pin "2") (pinfunction "2_2") (pintype "passive"))
      (node (ref "CLJ") (pin "2") (pinfunction "2_2") (pintype "passive"))
      (node (ref "CLL") (pin "2") (pinfunction "2_2") (pintype "passive"))
      (node (ref "CLM") (pin "2") (pinfunction "2_2") (pintype "passive"))
      (node (ref "CLN") (pin "2") (pinfunction "2_2") (pintype "passive"))
      (node (ref "CLO") (pin "1") (pinfunction "1_1") (pintype "passive"))
      (node (ref "CLP") (pin "1") (pinfunction "1_1") (pintype "passive"))
      (node (ref "CLQ") (pin "1") (pinfunction "1_1") (pintype "passive"))
      (node (ref "CLR") (pin "1") (pinfunction "1_1") (pintype "passive"))
      (node (ref "CLS") (pin "1") (pinfunction "1_1") (pintype "passive"))
      (node (ref "CLT") (pin "2") (pinfunction "2_2") (pintype "passive"))
      (node (ref "CLU") (pin "2") (pinfunction "2_2") (pintype "passive"))
      (node (ref "CR1") (pin "2") (pinfunction "2_2") (pintype "passive"))
      (node (ref "CR2") (pin "2") (pinfunction "2_2") (pintype "passive"))
      (node (ref "CR3") (pin "1") (pinfunction "1_1") (pintype "passive"))
      (node (ref "CR5") (pin "2") (pinfunction "2_2") (pintype "passive"))
      (node (ref "CR6") (pin "1") (pinfunction "1_1") (pintype "passive"))
      (node (ref "CR7") (pin "2") (pinfunction "2_2") (pintype "passive"))
      (node (ref "CR8") (pin "1") (pinfunction "1_1") (pintype "passive"))
      (node (ref "CRE") (pin "2") (pinfunction "2_2") (pintype "passive"))
      (node (ref "CRJ") (pin "2") (pinfunction "2_2") (pintype "passive"))
      (node (ref "CRL") (pin "2") (pinfunction "2_2") (pintype "passive"))
      (node (ref "CRM") (pin "2") (pinfunction "2_2") (pintype "passive"))
      (node (ref "CRN") (pin "2") (pinfunction "2_2") (pintype "passive"))
      (node (ref "CRO") (pin "1") (pinfunction "1_1") (pintype "passive"))
      (node (ref "CRP") (pin "1") (pinfunction "1_1") (pintype "passive"))
      (node (ref "CRQ") (pin "1") (pinfunction "1_1") (pintype "passive"))
      (node (ref "CRR") (pin "1") (pinfunction "1_1") (pintype "passive"))
      (node (ref "CRS") (pin "1") (pinfunction "1_1") (pintype "passive"))
      (node (ref "CRT") (pin "2") (pinfunction "2_2") (pintype "passive"))
      (node (ref "CRU") (pin "2") (pinfunction "2_2") (pintype "passive"))
      (node (ref "PL1") (pin "3") (pinfunction "3_3") (pintype "passive"))
      (node (ref "PL2") (pin "3") (pinfunction "3_3") (pintype "passive"))
      (node (ref "RL4") (pin "1") (pinfunction "1_1") (pintype "passive"))
      (node (ref "RL8") (pin "1") (pinfunction "1_1") (pintype "passive"))
      (node (ref "RLI") (pin "1") (pinfunction "1_1") (pintype "passive"))
      (node (ref "RLS") (pin "1") (pinfunction "1_1") (pintype "passive"))
      (node (ref "RR4") (pin "1") (pinfunction "1_1") (pintype "passive"))
      (node (ref "RR8") (pin "1") (pinfunction "1_1") (pintype "passive"))
      (node (ref "RRI") (pin "1") (pinfunction "1_1") (pintype "passive"))
      (node (ref "RRS") (pin "1") (pinfunction "1_1") (pintype "passive"))
      (node (ref "UA1") (pin "1") (pinfunction "~{OE}_1") (pintype "passive"))
      (node (ref "UA1") (pin "10") (pinfunction "GND_10") (pintype "passive"))
      (node (ref "UA1") (pin "15") (pinfunction "GND_15") (pintype "passive"))
      (node (ref "UA1") (pin "21") (pinfunction "GND_21") (pintype "passive"))
      (node (ref "UA1") (pin "24") (pinfunction "~{OE}_24") (pintype "passive"))
      (node (ref "UA1") (pin "28") (pinfunction "GND_28") (pintype "passive"))
      (node (ref "UA1") (pin "34") (pinfunction "GND_34") (pintype "passive"))
      (node (ref "UA1") (pin "39") (pinfunction "GND_39") (pintype "passive"))
      (node (ref "UA1") (pin "4") (pinfunction "GND_4") (pintype "passive"))
      (node (ref "UA1") (pin "45") (pinfunction "GND_45") (pintype "passive"))
      (node (ref "UA2") (pin "2") (pinfunction "GND_2") (pintype "passive"))
      (node (ref "UA3") (pin "2") (pinfunction "GND_2") (pintype "passive"))
      (node (ref "UA4") (pin "2") (pinfunction "GND_2") (pintype "passive"))
      (node (ref "UA5") (pin "2") (pinfunction "GND_2") (pintype "passive"))
      (node (ref "UA6") (pin "2") (pinfunction "GND_2") (pintype "passive"))
      (node (ref "UA7") (pin "2") (pinfunction "GND_2") (pintype "passive"))
      (node (ref "UA8") (pin "2") (pinfunction "GND_2") (pintype "passive"))
      (node (ref "UA9") (pin "2") (pinfunction "GND_2") (pintype "passive"))
      (node (ref "UAA") (pin "1") (pinfunction "~{OE}_1") (pintype "passive"))
      (node (ref "UAA") (pin "10") (pinfunction "GND_10") (pintype "passive"))
      (node (ref "UAA") (pin "15") (pinfunction "GND_15") (pintype "passive"))
      (node (ref "UAA") (pin "21") (pinfunction "GND_21") (pintype "passive"))
      (node (ref "UAA") (pin "24") (pinfunction "~{OE}_24") (pintype "passive"))
      (node (ref "UAA") (pin "28") (pinfunction "GND_28") (pintype "passive"))
      (node (ref "UAA") (pin "34") (pinfunction "GND_34") (pintype "passive"))
      (node (ref "UAA") (pin "39") (pinfunction "GND_39") (pintype "passive"))
      (node (ref "UAA") (pin "4") (pinfunction "GND_4") (pintype "passive"))
      (node (ref "UAA") (pin "45") (pinfunction "GND_45") (pintype "passive"))
      (node (ref "UAB") (pin "2") (pinfunction "GND_2") (pintype "passive"))
      (node (ref "UAC") (pin "2") (pinfunction "GND_2") (pintype "passive"))
      (node (ref "UAD") (pin "2") (pinfunction "GND_2") (pintype "passive"))
      (node (ref "UAE") (pin "2") (pinfunction "GND_2") (pintype "passive"))
      (node (ref "UAF") (pin "2") (pinfunction "GND_2") (pintype "passive"))
      (node (ref "UAG") (pin "2") (pinfunction "GND_2") (pintype "passive"))
      (node (ref "UAH") (pin "2") (pinfunction "GND_2") (pintype "passive"))
      (node (ref "UAI") (pin "2") (pinfunction "GND_2") (pintype "passive"))
      (node (ref "UL1") (pin "2") (pinfunction "VEE_2") (pintype "passive"))
      (node (ref "UR1") (pin "2") (pinfunction "VEE_2") (pintype "passive"))
    )
    (net (code "9") (name "/L0") (class "Default")
      (node (ref "UA1") (pin "26") (pinfunction "D15_26") (pintype "passive"))
    )
    (net (code "10") (name "/L1") (class "Default")
      (node (ref "UA1") (pin "27") (pinfunction "D14_27") (pintype "passive"))
    )
    (net (code "11") (name "/L2") (class "Default")
      (node (ref "UA1") (pin "29") (pinfunction "D13_29") (pintype "passive"))
    )
    (net (code "12") (name "/L3") (class "Default")
      (node (ref "UA1") (pin "30") (pinfunction "D12_30") (pintype "passive"))
    )
    (net (code "13") (name "/L4") (class "Default")
      (node (ref "UA1") (pin "32") (pinfunction "D11_32") (pintype "passive"))
    )
    (net (code "14") (name "/L5") (class "Default")
      (node (ref "UA1") (pin "33") (pinfunction "D10_33") (pintype "passive"))
    )
    (net (code "15") (name "/L6") (class "Default")
      (node (ref "UA1") (pin "35") (pinfunction "D9_35") (pintype "passive"))
    )
    (net (code "16") (name "/L7") (class "Default")
      (node (ref "UA1") (pin "36") (pinfunction "D8_36") (pintype "passive"))
    )
    (net (code "17") (name "/L8") (class "Default")
      (node (ref "UA1") (pin "37") (pinfunction "D7_37") (pintype "passive"))
    )
    (net (code "18") (name "/L9") (class "Default")
      (node (ref "UA1") (pin "38") (pinfunction "D6_38") (pintype "passive"))
    )
    (net (code "19") (name "/LA") (class "Default")
      (node (ref "UA1") (pin "40") (pinfunction "D5_40") (pintype "passive"))
    )
    (net (code "20") (name "/LB") (class "Default")
      (node (ref "UA1") (pin "41") (pinfunction "D4_41") (pintype "passive"))
    )
    (net (code "21") (name "/LC") (class "Default")
      (node (ref "UA1") (pin "43") (pinfunction "D3_43") (pintype "passive"))
    )
    (net (code "22") (name "/LD") (class "Default")
      (node (ref "UA1") (pin "44") (pinfunction "D2_44") (pintype "passive"))
    )
    (net (code "23") (name "/LE") (class "Default")
      (node (ref "UA1") (pin "46") (pinfunction "D1_46") (pintype "passive"))
    )
    (net (code "24") (name "/LF") (class "Default")
      (node (ref "UA1") (pin "47") (pinfunction "D0_47") (pintype "passive"))
    )
    (net (code "25") (name "/LO+") (class "Default")
      (node (ref "PL1") (pin "1") (pinfunction "1_1") (pintype "passive"))
      (node (ref "RLL") (pin "2") (pinfunction "2_2") (pintype "passive"))
      (node (ref "RLM") (pin "1") (pinfunction "1_1") (pintype "passive"))
    )
    (net (code "26") (name "/LO-") (class "Default")
      (node (ref "PL1") (pin "2") (pinfunction "2_2") (pintype "passive"))
      (node (ref "RLV") (pin "2") (pinfunction "2_2") (pintype "passive"))
      (node (ref "RLW") (pin "1") (pinfunction "1_1") (pintype "passive"))
    )
    (net (code "27") (name "/LS+") (class "Default")
      (node (ref "BA2") (pin "1") (pinfunction "1_1") (pintype "passive"))
      (node (ref "CL9") (pin "2") (pinfunction "2_2") (pintype "passive"))
      (node (ref "RL9") (pin "2") (pinfunction "2_2") (pintype "passive"))
      (node (ref "RLB") (pin "1") (pinfunction "1_1") (pintype "passive"))
      (node (ref "UL2") (pin "2") (pinfunction "IN-_2") (pintype "passive"))
    )
    (net (code "28") (name "/LS-") (class "Default")
      (node (ref "BA3") (pin "1") (pinfunction "1_1") (pintype "passive"))
      (node (ref "CLA") (pin "2") (pinfunction "2_2") (pintype "passive"))
      (node (ref "RLA") (pin "2") (pinfunction "2_2") (pintype "passive"))
      (node (ref "RLC") (pin "1") (pinfunction "1_1") (pintype "passive"))
      (node (ref "UL2") (pin "6") (pinfunction "IN-_6") (pintype "passive"))
    )
    (net (code "29") (name "/LU+") (class "Default")
      (node (ref "CL9") (pin "1") (pinfunction "1_1") (pintype "passive"))
      (node (ref "RLB") (pin "2") (pinfunction "2_2") (pintype "passive"))
      (node (ref "RLE") (pin "2") (pinfunction "2_2") (pintype "passive"))
      (node (ref "RLN") (pin "1") (pinfunction "1_1") (pintype "passive"))
      (node (ref "UL2") (pin "1") (pintype "passive"))
    )
    (net (code "30") (name "/LU-") (class "Default")
      (node (ref "CLA") (pin "1") (pinfunction "1_1") (pintype "passive"))
      (node (ref "RLC") (pin "2") (pinfunction "2_2") (pintype "passive"))
      (node (ref "RLD") (pin "1") (pinfunction "1_1") (pintype "passive"))
      (node (ref "RLO") (pin "2") (pinfunction "2_2") (pintype "passive"))
      (node (ref "UL2") (pin "7") (pintype "passive"))
    )
    (net (code "31") (name "/R0") (class "Default")
      (node (ref "UAA") (pin "26") (pinfunction "D15_26") (pintype "passive"))
    )
    (net (code "32") (name "/R1") (class "Default")
      (node (ref "UAA") (pin "27") (pinfunction "D14_27") (pintype "passive"))
    )
    (net (code "33") (name "/R2") (class "Default")
      (node (ref "UAA") (pin "29") (pinfunction "D13_29") (pintype "passive"))
    )
    (net (code "34") (name "/R3") (class "Default")
      (node (ref "UAA") (pin "30") (pinfunction "D12_30") (pintype "passive"))
    )
    (net (code "35") (name "/R4") (class "Default")
      (node (ref "UAA") (pin "32") (pinfunction "D11_32") (pintype "passive"))
    )
    (net (code "36") (name "/R5") (class "Default")
      (node (ref "UAA") (pin "33") (pinfunction "D10_33") (pintype "passive"))
    )
    (net (code "37") (name "/R6") (class "Default")
      (node (ref "UAA") (pin "35") (pinfunction "D9_35") (pintype "passive"))
    )
    (net (code "38") (name "/R7") (class "Default")
      (node (ref "UAA") (pin "36") (pinfunction "D8_36") (pintype "passive"))
    )
    (net (code "39") (name "/R8") (class "Default")
      (node (ref "UAA") (pin "37") (pinfunction "D7_37") (pintype "passive"))
    )
    (net (code "40") (name "/R9") (class "Default")
      (node (ref "UAA") (pin "38") (pinfunction "D6_38") (pintype "passive"))
    )
    (net (code "41") (name "/RA") (class "Default")
      (node (ref "UAA") (pin "40") (pinfunction "D5_40") (pintype "passive"))
    )
    (net (code "42") (name "/RB") (class "Default")
      (node (ref "UAA") (pin "41") (pinfunction "D4_41") (pintype "passive"))
    )
    (net (code "43") (name "/RC") (class "Default")
      (node (ref "UAA") (pin "43") (pinfunction "D3_43") (pintype "passive"))
    )
    (net (code "44") (name "/RD") (class "Default")
      (node (ref "UAA") (pin "44") (pinfunction "D2_44") (pintype "passive"))
    )
    (net (code "45") (name "/RE") (class "Default")
      (node (ref "UAA") (pin "46") (pinfunction "D1_46") (pintype "passive"))
    )
    (net (code "46") (name "/RF") (class "Default")
      (node (ref "UAA") (pin "47") (pinfunction "D0_47") (pintype "passive"))
    )
    (net (code "47") (name "/RO+") (class "Default")
      (node (ref "PL2") (pin "1") (pinfunction "1_1") (pintype "passive"))
      (node (ref "RRL") (pin "2") (pinfunction "2_2") (pintype "passive"))
      (node (ref "RRM") (pin "1") (pinfunction "1_1") (pintype "passive"))
    )
    (net (code "48") (name "/RO-") (class "Default")
      (node (ref "PL2") (pin "2") (pinfunction "2_2") (pintype "passive"))
      (node (ref "RRV") (pin "2") (pinfunction "2_2") (pintype "passive"))
      (node (ref "RRW") (pin "1") (pinfunction "1_1") (pintype "passive"))
    )
    (net (code "49") (name "/RS+") (class "Default")
      (node (ref "BA5") (pin "1") (pinfunction "1_1") (pintype "passive"))
      (node (ref "CR9") (pin "2") (pinfunction "2_2") (pintype "passive"))
      (node (ref "RR9") (pin "2") (pinfunction "2_2") (pintype "passive"))
      (node (ref "RRB") (pin "1") (pinfunction "1_1") (pintype "passive"))
      (node (ref "UR2") (pin "2") (pinfunction "IN-_2") (pintype "passive"))
    )
    (net (code "50") (name "/RS-") (class "Default")
      (node (ref "BA6") (pin "1") (pinfunction "1_1") (pintype "passive"))
      (node (ref "CRA") (pin "2") (pinfunction "2_2") (pintype "passive"))
      (node (ref "RRA") (pin "2") (pinfunction "2_2") (pintype "passive"))
      (node (ref "RRC") (pin "1") (pinfunction "1_1") (pintype "passive"))
      (node (ref "UR2") (pin "6") (pinfunction "IN-_6") (pintype "passive"))
    )
    (net (code "51") (name "/RU+") (class "Default")
      (node (ref "CR9") (pin "1") (pinfunction "1_1") (pintype "passive"))
      (node (ref "RRB") (pin "2") (pinfunction "2_2") (pintype "passive"))
      (node (ref "RRE") (pin "2") (pinfunction "2_2") (pintype "passive"))
      (node (ref "RRN") (pin "1") (pinfunction "1_1") (pintype "passive"))
      (node (ref "UR2") (pin "1") (pintype "passive"))
    )
    (net (code "52") (name "/RU-") (class "Default")
      (node (ref "CRA") (pin "1") (pinfunction "1_1") (pintype "passive"))
      (node (ref "RRC") (pin "2") (pinfunction "2_2") (pintype "passive"))
      (node (ref "RRD") (pin "1") (pinfunction "1_1") (pintype "passive"))
      (node (ref "RRO") (pin "2") (pinfunction "2_2") (pintype "passive"))
      (node (ref "UR2") (pin "7") (pintype "passive"))
    )
    (net (code "53") (name "/VCL") (class "Default")
      (node (ref "RL3") (pin "2") (pinfunction "2_2") (pintype "passive"))
    )
    (net (code "54") (name "/VCR") (class "Default")
      (node (ref "RR3") (pin "2") (pinfunction "2_2") (pintype "passive"))
    )
    (net (code "55") (name "Net-(BA2-Pad2)") (class "Default")
      (node (ref "BA2") (pin "2") (pinfunction "2_2") (pintype "passive"))
      (node (ref "CAE") (pin "2") (pinfunction "2_2") (pintype "passive"))
      (node (ref "RA1") (pin "2") (pinfunction "2_2") (pintype "passive"))
      (node (ref "RA2") (pin "2") (pinfunction "2_2") (pintype "passive"))
      (node (ref "RA3") (pin "2") (pinfunction "2_2") (pintype "passive"))
      (node (ref "RA4") (pin "2") (pinfunction "2_2") (pintype "passive"))
      (node (ref "RA5") (pin "2") (pinfunction "2_2") (pintype "passive"))
      (node (ref "RA6") (pin "2") (pinfunction "2_2") (pintype "passive"))
      (node (ref "RA7") (pin "2") (pinfunction "2_2") (pintype "passive"))
      (node (ref "RA8") (pin "2") (pinfunction "2_2") (pintype "passive"))
    )
    (net (code "56") (name "Net-(BA3-Pad2)") (class "Default")
      (node (ref "BA3") (pin "2") (pinfunction "2_2") (pintype "passive"))
      (node (ref "CAF") (pin "2") (pinfunction "2_2") (pintype "passive"))
      (node (ref "RA9") (pin "2") (pinfunction "2_2") (pintype "passive"))
      (node (ref "RAA") (pin "2") (pinfunction "2_2") (pintype "passive"))
      (node (ref "RAB") (pin "2") (pinfunction "2_2") (pintype "passive"))
      (node (ref "RAC") (pin "2") (pinfunction "2_2") (pintype "passive"))
      (node (ref "RAD") (pin "2") (pinfunction "2_2") (pintype "passive"))
      (node (ref "RAE") (pin "2") (pinfunction "2_2") (pintype "passive"))
      (node (ref "RAF") (pin "2") (pinfunction "2_2") (pintype "passive"))
      (node (ref "RAG") (pin "2") (pinfunction "2_2") (pintype "passive"))
    )
    (net (code "57") (name "Net-(BA5-Pad2)") (class "Default")
      (node (ref "BA5") (pin "2") (pinfunction "2_2") (pintype "passive"))
      (node (ref "CAT") (pin "2") (pinfunction "2_2") (pintype "passive"))
      (node (ref "RAH") (pin "2") (pinfunction "2_2") (pintype "passive"))
      (node (ref "RAI") (pin "2") (pinfunction "2_2") (pintype "passive"))
      (node (ref "RAJ") (pin "2") (pinfunction "2_2") (pintype "passive"))
      (node (ref "RAK") (pin "2") (pinfunction "2_2") (pintype "passive"))
      (node (ref "RAL") (pin "2") (pinfunction "2_2") (pintype "passive"))
      (node (ref "RAM") (pin "2") (pinfunction "2_2") (pintype "passive"))
      (node (ref "RAN") (pin "2") (pinfunction "2_2") (pintype "passive"))
      (node (ref "RAO") (pin "2") (pinfunction "2_2") (pintype "passive"))
    )
    (net (code "58") (name "Net-(BA6-Pad2)") (class "Default")
      (node (ref "BA6") (pin "2") (pinfunction "2_2") (pintype "passive"))
      (node (ref "CAU") (pin "2") (pinfunction "2_2") (pintype "passive"))
      (node (ref "RAP") (pin "2") (pinfunction "2_2") (pintype "passive"))
      (node (ref "RAQ") (pin "2") (pinfunction "2_2") (pintype "passive"))
      (node (ref "RAR") (pin "2") (pinfunction "2_2") (pintype "passive"))
      (node (ref "RAS") (pin "2") (pinfunction "2_2") (pintype "passive"))
      (node (ref "RAT") (pin "2") (pinfunction "2_2") (pintype "passive"))
      (node (ref "RAU") (pin "2") (pinfunction "2_2") (pintype "passive"))
      (node (ref "RAV") (pin "2") (pinfunction "2_2") (pintype "passive"))
      (node (ref "RAW") (pin "2") (pinfunction "2_2") (pintype "passive"))
    )
    (net (code "59") (name "Net-(CL2-Pad1)") (class "Default")
      (node (ref "CL2") (pin "1") (pinfunction "1_1") (pintype "passive"))
      (node (ref "RL1") (pin "2") (pinfunction "2_2") (pintype "passive"))
      (node (ref "RL2") (pin "2") (pinfunction "2_2") (pintype "passive"))
    )
    (net (code "60") (name "Net-(CL3-Pad2)") (class "Default")
      (node (ref "CL3") (pin "2") (pinfunction "2_2") (pintype "passive"))
      (node (ref "RL2") (pin "1") (pinfunction "1_1") (pintype "passive"))
      (node (ref "RL3") (pin "1") (pinfunction "1_1") (pintype "passive"))
    )
    (net (code "61") (name "Net-(CL4-Pad2)") (class "Default")
      (node (ref "CL4") (pin "2") (pinfunction "2_2") (pintype "passive"))
      (node (ref "RL6") (pin "2") (pinfunction "2_2") (pintype "passive"))
      (node (ref "UL1") (pin "1") (pintype "passive"))
    )
    (net (code "62") (name "Net-(CL5-Pad1)") (class "Default")
      (node (ref "CL5") (pin "1") (pinfunction "1_1") (pintype "passive"))
      (node (ref "CL6") (pin "2") (pinfunction "2_2") (pintype "passive"))
      (node (ref "RL5") (pin "1") (pinfunction "1_1") (pintype "passive"))
      (node (ref "RL6") (pin "1") (pinfunction "1_1") (pintype "passive"))
      (node (ref "RL7") (pin "2") (pinfunction "2_2") (pintype "passive"))
      (node (ref "RL9") (pin "1") (pinfunction "1_1") (pintype "passive"))
      (node (ref "RLA") (pin "1") (pinfunction "1_1") (pintype "passive"))
    )
    (net (code "63") (name "Net-(CLB-Pad1)") (class "Default")
      (node (ref "CLB") (pin "1") (pinfunction "1_1") (pintype "passive"))
      (node (ref "RLE") (pin "1") (pinfunction "1_1") (pintype "passive"))
      (node (ref "RLG") (pin "2") (pinfunction "2_2") (pintype "passive"))
    )
    (net (code "64") (name "Net-(CLB-Pad2)") (class "Default")
      (node (ref "CLB") (pin "2") (pinfunction "2_2") (pintype "passive"))
      (node (ref "RLD") (pin "2") (pinfunction "2_2") (pintype "passive"))
      (node (ref "RLF") (pin "2") (pinfunction "2_2") (pintype "passive"))
    )
    (net (code "65") (name "Net-(CLC-Pad1)") (class "Default")
      (node (ref "CLC") (pin "1") (pinfunction "1_1") (pintype "passive"))
      (node (ref "RLG") (pin "1") (pinfunction "1_1") (pintype "passive"))
      (node (ref "RLI") (pin "2") (pinfunction "2_2") (pintype "passive"))
      (node (ref "RLK") (pin "2") (pinfunction "2_2") (pintype "passive"))
    )
    (net (code "66") (name "Net-(CLC-Pad2)") (class "Default")
      (node (ref "CLC") (pin "2") (pinfunction "2_2") (pintype "passive"))
      (node (ref "RLF") (pin "1") (pinfunction "1_1") (pintype "passive"))
      (node (ref "RLH") (pin "1") (pinfunction "1_1") (pintype "passive"))
      (node (ref "RLJ") (pin "2") (pinfunction "2_2") (pintype "passive"))
    )
    (net (code "67") (name "Net-(CLD-Pad2)") (class "Default")
      (node (ref "CLD") (pin "2") (pinfunction "2_2") (pintype "passive"))
      (node (ref "CLF") (pin "2") (pinfunction "2_2") (pintype "passive"))
      (node (ref "RLH") (pin "2") (pinfunction "2_2") (pintype "passive"))
      (node (ref "RLL") (pin "1") (pinfunction "1_1") (pintype "passive"))
    )
    (net (code "68") (name "Net-(CLF-Pad1)") (class "Default")
      (node (ref "CLF") (pin "1") (pinfunction "1_1") (pintype "passive"))
      (node (ref "RLM") (pin "2") (pinfunction "2_2") (pintype "passive"))
      (node (ref "UL3") (pin "1") (pintype "passive"))
    )
    (net (code "69") (name "Net-(CLG-Pad1)") (class "Default")
      (node (ref "CLG") (pin "1") (pinfunction "1_1") (pintype "passive"))
      (node (ref "RLO") (pin "1") (pinfunction "1_1") (pintype "passive"))
      (node (ref "RLQ") (pin "2") (pinfunction "2_2") (pintype "passive"))
    )
    (net (code "70") (name "Net-(CLG-Pad2)") (class "Default")
      (node (ref "CLG") (pin "2") (pinfunction "2_2") (pintype "passive"))
      (node (ref "RLN") (pin "2") (pinfunction "2_2") (pintype "passive"))
      (node (ref "RLP") (pin "2") (pinfunction "2_2") (pintype "passive"))
    )
    (net (code "71") (name "Net-(CLH-Pad1)") (class "Default")
      (node (ref "CLH") (pin "1") (pinfunction "1_1") (pintype "passive"))
      (node (ref "RLQ") (pin "1") (pinfunction "1_1") (pintype "passive"))
      (node (ref "RLS") (pin "2") (pinfunction "2_2") (pintype "passive"))
      (node (ref "RLU") (pin "2") (pinfunction "2_2") (pintype "passive"))
    )
    (net (code "72") (name "Net-(CLH-Pad2)") (class "Default")
      (node (ref "CLH") (pin "2") (pinfunction "2_2") (pintype "passive"))
      (node (ref "RLP") (pin "1") (pinfunction "1_1") (pintype "passive"))
      (node (ref "RLR") (pin "1") (pinfunction "1_1") (pintype "passive"))
      (node (ref "RLT") (pin "2") (pinfunction "2_2") (pintype "passive"))
    )
    (net (code "73") (name "Net-(CLI-Pad2)") (class "Default")
      (node (ref "CLI") (pin "2") (pinfunction "2_2") (pintype "passive"))
      (node (ref "CLK") (pin "1") (pinfunction "1_1") (pintype "passive"))
      (node (ref "RLR") (pin "2") (pinfunction "2_2") (pintype "passive"))
      (node (ref "RLV") (pin "1") (pinfunction "1_1") (pintype "passive"))
    )
    (net (code "74") (name "Net-(CLK-Pad2)") (class "Default")
      (node (ref "CLK") (pin "2") (pinfunction "2_2") (pintype "passive"))
      (node (ref "RLW") (pin "2") (pinfunction "2_2") (pintype "passive"))
      (node (ref "UL3") (pin "7") (pintype "passive"))
    )
    (net (code "75") (name "Net-(CR2-Pad1)") (class "Default")
      (node (ref "CR2") (pin "1") (pinfunction "1_1") (pintype "passive"))
      (node (ref "RR1") (pin "2") (pinfunction "2_2") (pintype "passive"))
      (node (ref "RR2") (pin "2") (pinfunction "2_2") (pintype "passive"))
    )
    (net (code "76") (name "Net-(CR3-Pad2)") (class "Default")
      (node (ref "CR3") (pin "2") (pinfunction "2_2") (pintype "passive"))
      (node (ref "RR2") (pin "1") (pinfunction "1_1") (pintype "passive"))
      (node (ref "RR3") (pin "1") (pinfunction "1_1") (pintype "passive"))
    )
    (net (code "77") (name "Net-(CR4-Pad2)") (class "Default")
      (node (ref "CR4") (pin "2") (pinfunction "2_2") (pintype "passive"))
      (node (ref "RR6") (pin "2") (pinfunction "2_2") (pintype "passive"))
      (node (ref "UR1") (pin "1") (pintype "passive"))
    )
    (net (code "78") (name "Net-(CR5-Pad1)") (class "Default")
      (node (ref "CR5") (pin "1") (pinfunction "1_1") (pintype "passive"))
      (node (ref "CR6") (pin "2") (pinfunction "2_2") (pintype "passive"))
      (node (ref "RR5") (pin "1") (pinfunction "1_1") (pintype "passive"))
      (node (ref "RR6") (pin "1") (pinfunction "1_1") (pintype "passive"))
      (node (ref "RR7") (pin "2") (pinfunction "2_2") (pintype "passive"))
      (node (ref "RR9") (pin "1") (pinfunction "1_1") (pintype "passive"))
      (node (ref "RRA") (pin "1") (pinfunction "1_1") (pintype "passive"))
    )
    (net (code "79") (name "Net-(CRB-Pad1)") (class "Default")
      (node (ref "CRB") (pin "1") (pinfunction "1_1") (pintype "passive"))
      (node (ref "RRE") (pin "1") (pinfunction "1_1") (pintype "passive"))
      (node (ref "RRG") (pin "2") (pinfunction "2_2") (pintype "passive"))
    )
    (net (code "80") (name "Net-(CRB-Pad2)") (class "Default")
      (node (ref "CRB") (pin "2") (pinfunction "2_2") (pintype "passive"))
      (node (ref "RRD") (pin "2") (pinfunction "2_2") (pintype "passive"))
      (node (ref "RRF") (pin "2") (pinfunction "2_2") (pintype "passive"))
    )
    (net (code "81") (name "Net-(CRC-Pad1)") (class "Default")
      (node (ref "CRC") (pin "1") (pinfunction "1_1") (pintype "passive"))
      (node (ref "RRG") (pin "1") (pinfunction "1_1") (pintype "passive"))
      (node (ref "RRI") (pin "2") (pinfunction "2_2") (pintype "passive"))
      (node (ref "RRK") (pin "2") (pinfunction "2_2") (pintype "passive"))
    )
    (net (code "82") (name "Net-(CRC-Pad2)") (class "Default")
      (node (ref "CRC") (pin "2") (pinfunction "2_2") (pintype "passive"))
      (node (ref "RRF") (pin "1") (pinfunction "1_1") (pintype "passive"))
      (node (ref "RRH") (pin "1") (pinfunction "1_1") (pintype "passive"))
      (node (ref "RRJ") (pin "2") (pinfunction "2_2") (pintype "passive"))
    )
    (net (code "83") (name "Net-(CRD-Pad2)") (class "Default")
      (node (ref "CRD") (pin "2") (pinfunction "2_2") (pintype "passive"))
      (node (ref "CRF") (pin "1") (pinfunction "1_1") (pintype "passive"))
      (node (ref "RRH") (pin "2") (pinfunction "2_2") (pintype "passive"))
      (node (ref "RRL") (pin "1") (pinfunction "1_1") (pintype "passive"))
    )
    (net (code "84") (name "Net-(CRF-Pad2)") (class "Default")
      (node (ref "CRF") (pin "2") (pinfunction "2_2") (pintype "passive"))
      (node (ref "RRM") (pin "2") (pinfunction "2_2") (pintype "passive"))
      (node (ref "UR3") (pin "1") (pintype "passive"))
    )
    (net (code "85") (name "Net-(CRG-Pad1)") (class "Default")
      (node (ref "CRG") (pin "1") (pinfunction "1_1") (pintype "passive"))
      (node (ref "RRO") (pin "1") (pinfunction "1_1") (pintype "passive"))
      (node (ref "RRQ") (pin "2") (pinfunction "2_2") (pintype "passive"))
    )
    (net (code "86") (name "Net-(CRG-Pad2)") (class "Default")
      (node (ref "CRG") (pin "2") (pinfunction "2_2") (pintype "passive"))
      (node (ref "RRN") (pin "2") (pinfunction "2_2") (pintype "passive"))
      (node (ref "RRP") (pin "2") (pinfunction "2_2") (pintype "passive"))
    )
    (net (code "87") (name "Net-(CRH-Pad1)") (class "Default")
      (node (ref "CRH") (pin "1") (pinfunction "1_1") (pintype "passive"))
      (node (ref "RRQ") (pin "1") (pinfunction "1_1") (pintype "passive"))
      (node (ref "RRS") (pin "2") (pinfunction "2_2") (pintype "passive"))
      (node (ref "RRU") (pin "2") (pinfunction "2_2") (pintype "passive"))
    )
    (net (code "88") (name "Net-(CRH-Pad2)") (class "Default")
      (node (ref "CRH") (pin "2") (pinfunction "2_2") (pintype "passive"))
      (node (ref "RRP") (pin "1") (pinfunction "1_1") (pintype "passive"))
      (node (ref "RRR") (pin "1") (pinfunction "1_1") (pintype "passive"))
      (node (ref "RRT") (pin "2") (pinfunction "2_2") (pintype "passive"))
    )
    (net (code "89") (name "Net-(CRI-Pad2)") (class "Default")
      (node (ref "CRI") (pin "2") (pinfunction "2_2") (pintype "passive"))
      (node (ref "CRK") (pin "1") (pinfunction "1_1") (pintype "passive"))
      (node (ref "RRR") (pin "2") (pinfunction "2_2") (pintype "passive"))
      (node (ref "RRV") (pin "1") (pinfunction "1_1") (pintype "passive"))
    )
    (net (code "90") (name "Net-(CRK-Pad2)") (class "Default")
      (node (ref "CRK") (pin "2") (pinfunction "2_2") (pintype "passive"))
      (node (ref "RRW") (pin "2") (pinfunction "2_2") (pintype "passive"))
      (node (ref "UR3") (pin "7") (pintype "passive"))
    )
    (net (code "91") (name "Net-(UA1-Q0)") (class "Default")
      (node (ref "UA1") (pin "2") (pinfunction "Q0_2") (pintype "passive"))
      (node (ref "UA9") (pin "3") (pinfunction "A1_3") (pintype "passive"))
    )
    (net (code "92") (name "Net-(UA1-Q1)") (class "Default")
      (node (ref "UA1") (pin "3") (pinfunction "Q1_3") (pintype "passive"))
      (node (ref "UA9") (pin "1") (pinfunction "A0_1") (pintype "passive"))
    )
    (net (code "93") (name "Net-(UA1-Q2)") (class "Default")
      (node (ref "UA1") (pin "5") (pinfunction "Q2_5") (pintype "passive"))
      (node (ref "UA8") (pin "3") (pinfunction "A1_3") (pintype "passive"))
    )
    (net (code "94") (name "Net-(UA1-Q3)") (class "Default")
      (node (ref "UA1") (pin "6") (pinfunction "Q3_6") (pintype "passive"))
      (node (ref "UA8") (pin "1") (pinfunction "A0_1") (pintype "passive"))
    )
    (net (code "95") (name "Net-(UA1-Q4)") (class "Default")
      (node (ref "UA1") (pin "8") (pinfunction "Q4_8") (pintype "passive"))
      (node (ref "UA7") (pin "3") (pinfunction "A1_3") (pintype "passive"))
    )
    (net (code "96") (name "Net-(UA1-Q5)") (class "Default")
      (node (ref "UA1") (pin "9") (pinfunction "Q5_9") (pintype "passive"))
      (node (ref "UA7") (pin "1") (pinfunction "A0_1") (pintype "passive"))
    )
    (net (code "97") (name "Net-(UA1-Q6)") (class "Default")
      (node (ref "UA1") (pin "11") (pinfunction "Q6_11") (pintype "passive"))
      (node (ref "UA6") (pin "3") (pinfunction "A1_3") (pintype "passive"))
    )
    (net (code "98") (name "Net-(UA1-Q7)") (class "Default")
      (node (ref "UA1") (pin "12") (pinfunction "Q7_12") (pintype "passive"))
      (node (ref "UA6") (pin "1") (pinfunction "A0_1") (pintype "passive"))
    )
    (net (code "99") (name "Net-(UA1-Q8)") (class "Default")
      (node (ref "UA1") (pin "13") (pinfunction "Q8_13") (pintype "passive"))
      (node (ref "UA5") (pin "3") (pinfunction "A1_3") (pintype "passive"))
    )
    (net (code "100") (name "Net-(UA1-Q9)") (class "Default")
      (node (ref "UA1") (pin "14") (pinfunction "Q9_14") (pintype "passive"))
      (node (ref "UA5") (pin "1") (pinfunction "A0_1") (pintype "passive"))
    )
    (net (code "101") (name "Net-(UA1-Q10)") (class "Default")
      (node (ref "UA1") (pin "16") (pinfunction "Q10_16") (pintype "passive"))
      (node (ref "UA4") (pin "3") (pinfunction "A1_3") (pintype "passive"))
    )
    (net (code "102") (name "Net-(UA1-Q11)") (class "Default")
      (node (ref "UA1") (pin "17") (pinfunction "Q11_17") (pintype "passive"))
      (node (ref "UA4") (pin "1") (pinfunction "A0_1") (pintype "passive"))
    )
    (net (code "103") (name "Net-(UA1-Q12)") (class "Default")
      (node (ref "UA1") (pin "19") (pinfunction "Q12_19") (pintype "passive"))
      (node (ref "UA3") (pin "3") (pinfunction "A1_3") (pintype "passive"))
    )
    (net (code "104") (name "Net-(UA1-Q13)") (class "Default")
      (node (ref "UA1") (pin "20") (pinfunction "Q13_20") (pintype "passive"))
      (node (ref "UA3") (pin "1") (pinfunction "A0_1") (pintype "passive"))
    )
    (net (code "105") (name "Net-(UA1-Q14)") (class "Default")
      (node (ref "UA1") (pin "22") (pinfunction "Q14_22") (pintype "passive"))
      (node (ref "UA2") (pin "3") (pinfunction "A1_3") (pintype "passive"))
    )
    (net (code "106") (name "Net-(UA1-Q15)") (class "Default")
      (node (ref "UA1") (pin "23") (pinfunction "Q15_23") (pintype "passive"))
      (node (ref "UA2") (pin "1") (pinfunction "A0_1") (pintype "passive"))
    )
    (net (code "107") (name "Net-(UA2-VDD)") (class "Default")
      (node (ref "BA1") (pin "2") (pinfunction "2_2") (pintype "passive"))
      (node (ref "CA1") (pin "1") (pinfunction "1_1") (pintype "passive"))
      (node (ref "CA2") (pin "1") (pinfunction "1_1") (pintype "passive"))
      (node (ref "CA3") (pin "1") (pinfunction "1_1") (pintype "passive"))
      (node (ref "CA4") (pin "1") (pinfunction "1_1") (pintype "passive"))
      (node (ref "CA5") (pin "1") (pinfunction "1_1") (pintype "passive"))
      (node (ref "CA6") (pin "1") (pinfunction "1_1") (pintype "passive"))
      (node (ref "CA7") (pin "1") (pinfunction "1_1") (pintype "passive"))
      (node (ref "CA8") (pin "2") (pinfunction "2_2") (pintype "passive"))
      (node (ref "CA9") (pin "2") (pinfunction "2_2") (pintype "passive"))
      (node (ref "CAA") (pin "2") (pinfunction "2_2") (pintype "passive"))
      (node (ref "CAB") (pin "2") (pinfunction "2_2") (pintype "passive"))
      (node (ref "CAC") (pin "2") (pinfunction "2_2") (pintype "passive"))
      (node (ref "CAD") (pin "2") (pinfunction "2_2") (pintype "passive"))
      (node (ref "UA1") (pin "18") (pinfunction "VDD_18") (pintype "passive"))
      (node (ref "UA1") (pin "31") (pinfunction "VDD_31") (pintype "passive"))
      (node (ref "UA1") (pin "42") (pinfunction "VDD_42") (pintype "passive"))
      (node (ref "UA1") (pin "7") (pinfunction "VDD_7") (pintype "passive"))
      (node (ref "UA2") (pin "5") (pinfunction "VDD_5") (pintype "passive"))
      (node (ref "UA3") (pin "5") (pinfunction "VDD_5") (pintype "passive"))
      (node (ref "UA4") (pin "5") (pinfunction "VDD_5") (pintype "passive"))
      (node (ref "UA5") (pin "5") (pinfunction "VDD_5") (pintype "passive"))
      (node (ref "UA6") (pin "5") (pinfunction "VDD_5") (pintype "passive"))
      (node (ref "UA7") (pin "5") (pinfunction "VDD_5") (pintype "passive"))
      (node (ref "UA8") (pin "5") (pinfunction "VDD_5") (pintype "passive"))
      (node (ref "UA9") (pin "5") (pinfunction "VDD_5") (pintype "passive"))
    )
    (net (code "108") (name "Net-(UA2-Y0)") (class "Default")
      (node (ref "RA1") (pin "1") (pinfunction "1_1") (pintype "passive"))
      (node (ref "UA2") (pin "6") (pinfunction "Y0_6") (pintype "passive"))
    )
    (net (code "109") (name "Net-(UA2-Y1)") (class "Default")
      (node (ref "RA2") (pin "1") (pinfunction "1_1") (pintype "passive"))
      (node (ref "UA2") (pin "4") (pinfunction "Y1_4") (pintype "passive"))
    )
    (net (code "110") (name "Net-(UA3-Y0)") (class "Default")
      (node (ref "RA3") (pin "1") (pinfunction "1_1") (pintype "passive"))
      (node (ref "UA3") (pin "6") (pinfunction "Y0_6") (pintype "passive"))
    )
    (net (code "111") (name "Net-(UA3-Y1)") (class "Default")
      (node (ref "RA4") (pin "1") (pinfunction "1_1") (pintype "passive"))
      (node (ref "UA3") (pin "4") (pinfunction "Y1_4") (pintype "passive"))
    )
    (net (code "112") (name "Net-(UA4-Y0)") (class "Default")
      (node (ref "RA5") (pin "1") (pinfunction "1_1") (pintype "passive"))
      (node (ref "UA4") (pin "6") (pinfunction "Y0_6") (pintype "passive"))
    )
    (net (code "113") (name "Net-(UA4-Y1)") (class "Default")
      (node (ref "RA6") (pin "1") (pinfunction "1_1") (pintype "passive"))
      (node (ref "UA4") (pin "4") (pinfunction "Y1_4") (pintype "passive"))
    )
    (net (code "114") (name "Net-(UA5-Y0)") (class "Default")
      (node (ref "RA7") (pin "1") (pinfunction "1_1") (pintype "passive"))
      (node (ref "UA5") (pin "6") (pinfunction "Y0_6") (pintype "passive"))
    )
    (net (code "115") (name "Net-(UA5-Y1)") (class "Default")
      (node (ref "RA8") (pin "1") (pinfunction "1_1") (pintype "passive"))
      (node (ref "UA5") (pin "4") (pinfunction "Y1_4") (pintype "passive"))
    )
    (net (code "116") (name "Net-(UA6-Y0)") (class "Default")
      (node (ref "RA9") (pin "1") (pinfunction "1_1") (pintype "passive"))
      (node (ref "UA6") (pin "6") (pinfunction "Y0_6") (pintype "passive"))
    )
    (net (code "117") (name "Net-(UA6-Y1)") (class "Default")
      (node (ref "RAA") (pin "1") (pinfunction "1_1") (pintype "passive"))
      (node (ref "UA6") (pin "4") (pinfunction "Y1_4") (pintype "passive"))
    )
    (net (code "118") (name "Net-(UA7-Y0)") (class "Default")
      (node (ref "RAB") (pin "1") (pinfunction "1_1") (pintype "passive"))
      (node (ref "UA7") (pin "6") (pinfunction "Y0_6") (pintype "passive"))
    )
    (net (code "119") (name "Net-(UA7-Y1)") (class "Default")
      (node (ref "RAC") (pin "1") (pinfunction "1_1") (pintype "passive"))
      (node (ref "UA7") (pin "4") (pinfunction "Y1_4") (pintype "passive"))
    )
    (net (code "120") (name "Net-(UA8-Y0)") (class "Default")
      (node (ref "RAD") (pin "1") (pinfunction "1_1") (pintype "passive"))
      (node (ref "UA8") (pin "6") (pinfunction "Y0_6") (pintype "passive"))
    )
    (net (code "121") (name "Net-(UA8-Y1)") (class "Default")
      (node (ref "RAE") (pin "1") (pinfunction "1_1") (pintype "passive"))
      (node (ref "UA8") (pin "4") (pinfunction "Y1_4") (pintype "passive"))
    )
    (net (code "122") (name "Net-(UA9-Y0)") (class "Default")
      (node (ref "RAF") (pin "1") (pinfunction "1_1") (pintype "passive"))
      (node (ref "UA9") (pin "6") (pinfunction "Y0_6") (pintype "passive"))
    )
    (net (code "123") (name "Net-(UA9-Y1)") (class "Default")
      (node (ref "RAG") (pin "1") (pinfunction "1_1") (pintype "passive"))
      (node (ref "UA9") (pin "4") (pinfunction "Y1_4") (pintype "passive"))
    )
    (net (code "124") (name "Net-(UAA-Q0)") (class "Default")
      (node (ref "UAA") (pin "2") (pinfunction "Q0_2") (pintype "passive"))
      (node (ref "UAI") (pin "3") (pinfunction "A1_3") (pintype "passive"))
    )
    (net (code "125") (name "Net-(UAA-Q1)") (class "Default")
      (node (ref "UAA") (pin "3") (pinfunction "Q1_3") (pintype "passive"))
      (node (ref "UAI") (pin "1") (pinfunction "A0_1") (pintype "passive"))
    )
    (net (code "126") (name "Net-(UAA-Q2)") (class "Default")
      (node (ref "UAA") (pin "5") (pinfunction "Q2_5") (pintype "passive"))
      (node (ref "UAH") (pin "3") (pinfunction "A1_3") (pintype "passive"))
    )
    (net (code "127") (name "Net-(UAA-Q3)") (class "Default")
      (node (ref "UAA") (pin "6") (pinfunction "Q3_6") (pintype "passive"))
      (node (ref "UAH") (pin "1") (pinfunction "A0_1") (pintype "passive"))
    )
    (net (code "128") (name "Net-(UAA-Q4)") (class "Default")
      (node (ref "UAA") (pin "8") (pinfunction "Q4_8") (pintype "passive"))
      (node (ref "UAG") (pin "3") (pinfunction "A1_3") (pintype "passive"))
    )
    (net (code "129") (name "Net-(UAA-Q5)") (class "Default")
      (node (ref "UAA") (pin "9") (pinfunction "Q5_9") (pintype "passive"))
      (node (ref "UAG") (pin "1") (pinfunction "A0_1") (pintype "passive"))
    )
    (net (code "130") (name "Net-(UAA-Q6)") (class "Default")
      (node (ref "UAA") (pin "11") (pinfunction "Q6_11") (pintype "passive"))
      (node (ref "UAF") (pin "3") (pinfunction "A1_3") (pintype "passive"))
    )
    (net (code "131") (name "Net-(UAA-Q7)") (class "Default")
      (node (ref "UAA") (pin "12") (pinfunction "Q7_12") (pintype "passive"))
      (node (ref "UAF") (pin "1") (pinfunction "A0_1") (pintype "passive"))
    )
    (net (code "132") (name "Net-(UAA-Q8)") (class "Default")
      (node (ref "UAA") (pin "13") (pinfunction "Q8_13") (pintype "passive"))
      (node (ref "UAE") (pin "3") (pinfunction "A1_3") (pintype "passive"))
    )
    (net (code "133") (name "Net-(UAA-Q9)") (class "Default")
      (node (ref "UAA") (pin "14") (pinfunction "Q9_14") (pintype "passive"))
      (node (ref "UAE") (pin "1") (pinfunction "A0_1") (pintype "passive"))
    )
    (net (code "134") (name "Net-(UAA-Q10)") (class "Default")
      (node (ref "UAA") (pin "16") (pinfunction "Q10_16") (pintype "passive"))
      (node (ref "UAD") (pin "3") (pinfunction "A1_3") (pintype "passive"))
    )
    (net (code "135") (name "Net-(UAA-Q11)") (class "Default")
      (node (ref "UAA") (pin "17") (pinfunction "Q11_17") (pintype "passive"))
      (node (ref "UAD") (pin "1") (pinfunction "A0_1") (pintype "passive"))
    )
    (net (code "136") (name "Net-(UAA-Q12)") (class "Default")
      (node (ref "UAA") (pin "19") (pinfunction "Q12_19") (pintype "passive"))
      (node (ref "UAC") (pin "3") (pinfunction "A1_3") (pintype "passive"))
    )
    (net (code "137") (name "Net-(UAA-Q13)") (class "Default")
      (node (ref "UAA") (pin "20") (pinfunction "Q13_20") (pintype "passive"))
      (node (ref "UAC") (pin "1") (pinfunction "A0_1") (pintype "passive"))
    )
    (net (code "138") (name "Net-(UAA-Q14)") (class "Default")
      (node (ref "UAA") (pin "22") (pinfunction "Q14_22") (pintype "passive"))
      (node (ref "UAB") (pin "3") (pinfunction "A1_3") (pintype "passive"))
    )
    (net (code "139") (name "Net-(UAA-Q15)") (class "Default")
      (node (ref "UAA") (pin "23") (pinfunction "Q15_23") (pintype "passive"))
      (node (ref "UAB") (pin "1") (pinfunction "A0_1") (pintype "passive"))
    )
    (net (code "140") (name "Net-(UAB-VDD)") (class "Default")
      (node (ref "BA4") (pin "2") (pinfunction "2_2") (pintype "passive"))
      (node (ref "CAG") (pin "1") (pinfunction "1_1") (pintype "passive"))
      (node (ref "CAH") (pin "1") (pinfunction "1_1") (pintype "passive"))
      (node (ref "CAI") (pin "1") (pinfunction "1_1") (pintype "passive"))
      (node (ref "CAJ") (pin "1") (pinfunction "1_1") (pintype "passive"))
      (node (ref "CAK") (pin "1") (pinfunction "1_1") (pintype "passive"))
      (node (ref "CAL") (pin "1") (pinfunction "1_1") (pintype "passive"))
      (node (ref "CAM") (pin "1") (pinfunction "1_1") (pintype "passive"))
      (node (ref "CAN") (pin "2") (pinfunction "2_2") (pintype "passive"))
      (node (ref "CAO") (pin "2") (pinfunction "2_2") (pintype "passive"))
      (node (ref "CAP") (pin "2") (pinfunction "2_2") (pintype "passive"))
      (node (ref "CAQ") (pin "2") (pinfunction "2_2") (pintype "passive"))
      (node (ref "CAR") (pin "2") (pinfunction "2_2") (pintype "passive"))
      (node (ref "CAS") (pin "2") (pinfunction "2_2") (pintype "passive"))
      (node (ref "UAA") (pin "18") (pinfunction "VDD_18") (pintype "passive"))
      (node (ref "UAA") (pin "31") (pinfunction "VDD_31") (pintype "passive"))
      (node (ref "UAA") (pin "42") (pinfunction "VDD_42") (pintype "passive"))
      (node (ref "UAA") (pin "7") (pinfunction "VDD_7") (pintype "passive"))
      (node (ref "UAB") (pin "5") (pinfunction "VDD_5") (pintype "passive"))
      (node (ref "UAC") (pin "5") (pinfunction "VDD_5") (pintype "passive"))
      (node (ref "UAD") (pin "5") (pinfunction "VDD_5") (pintype "passive"))
      (node (ref "UAE") (pin "5") (pinfunction "VDD_5") (pintype "passive"))
      (node (ref "UAF") (pin "5") (pinfunction "VDD_5") (pintype "passive"))
      (node (ref "UAG") (pin "5") (pinfunction "VDD_5") (pintype "passive"))
      (node (ref "UAH") (pin "5") (pinfunction "VDD_5") (pintype "passive"))
      (node (ref "UAI") (pin "5") (pinfunction "VDD_5") (pintype "passive"))
    )
    (net (code "141") (name "Net-(UAB-Y0)") (class "Default")
      (node (ref "RAH") (pin "1") (pinfunction "1_1") (pintype "passive"))
      (node (ref "UAB") (pin "6") (pinfunction "Y0_6") (pintype "passive"))
    )
    (net (code "142") (name "Net-(UAB-Y1)") (class "Default")
      (node (ref "RAI") (pin "1") (pinfunction "1_1") (pintype "passive"))
      (node (ref "UAB") (pin "4") (pinfunction "Y1_4") (pintype "passive"))
    )
    (net (code "143") (name "Net-(UAC-Y0)") (class "Default")
      (node (ref "RAJ") (pin "1") (pinfunction "1_1") (pintype "passive"))
      (node (ref "UAC") (pin "6") (pinfunction "Y0_6") (pintype "passive"))
    )
    (net (code "144") (name "Net-(UAC-Y1)") (class "Default")
      (node (ref "RAK") (pin "1") (pinfunction "1_1") (pintype "passive"))
      (node (ref "UAC") (pin "4") (pinfunction "Y1_4") (pintype "passive"))
    )
    (net (code "145") (name "Net-(UAD-Y0)") (class "Default")
      (node (ref "RAL") (pin "1") (pinfunction "1_1") (pintype "passive"))
      (node (ref "UAD") (pin "6") (pinfunction "Y0_6") (pintype "passive"))
    )
    (net (code "146") (name "Net-(UAD-Y1)") (class "Default")
      (node (ref "RAM") (pin "1") (pinfunction "1_1") (pintype "passive"))
      (node (ref "UAD") (pin "4") (pinfunction "Y1_4") (pintype "passive"))
    )
    (net (code "147") (name "Net-(UAE-Y0)") (class "Default")
      (node (ref "RAN") (pin "1") (pinfunction "1_1") (pintype "passive"))
      (node (ref "UAE") (pin "6") (pinfunction "Y0_6") (pintype "passive"))
    )
    (net (code "148") (name "Net-(UAE-Y1)") (class "Default")
      (node (ref "RAO") (pin "1") (pinfunction "1_1") (pintype "passive"))
      (node (ref "UAE") (pin "4") (pinfunction "Y1_4") (pintype "passive"))
    )
    (net (code "149") (name "Net-(UAF-Y0)") (class "Default")
      (node (ref "RAP") (pin "1") (pinfunction "1_1") (pintype "passive"))
      (node (ref "UAF") (pin "6") (pinfunction "Y0_6") (pintype "passive"))
    )
    (net (code "150") (name "Net-(UAF-Y1)") (class "Default")
      (node (ref "RAQ") (pin "1") (pinfunction "1_1") (pintype "passive"))
      (node (ref "UAF") (pin "4") (pinfunction "Y1_4") (pintype "passive"))
    )
    (net (code "151") (name "Net-(UAG-Y0)") (class "Default")
      (node (ref "RAR") (pin "1") (pinfunction "1_1") (pintype "passive"))
      (node (ref "UAG") (pin "6") (pinfunction "Y0_6") (pintype "passive"))
    )
    (net (code "152") (name "Net-(UAG-Y1)") (class "Default")
      (node (ref "RAS") (pin "1") (pinfunction "1_1") (pintype "passive"))
      (node (ref "UAG") (pin "4") (pinfunction "Y1_4") (pintype "passive"))
    )
    (net (code "153") (name "Net-(UAH-Y0)") (class "Default")
      (node (ref "RAT") (pin "1") (pinfunction "1_1") (pintype "passive"))
      (node (ref "UAH") (pin "6") (pinfunction "Y0_6") (pintype "passive"))
    )
    (net (code "154") (name "Net-(UAH-Y1)") (class "Default")
      (node (ref "RAU") (pin "1") (pinfunction "1_1") (pintype "passive"))
      (node (ref "UAH") (pin "4") (pinfunction "Y1_4") (pintype "passive"))
    )
    (net (code "155") (name "Net-(UAI-Y0)") (class "Default")
      (node (ref "RAV") (pin "1") (pinfunction "1_1") (pintype "passive"))
      (node (ref "UAI") (pin "6") (pinfunction "Y0_6") (pintype "passive"))
    )
    (net (code "156") (name "Net-(UAI-Y1)") (class "Default")
      (node (ref "RAW") (pin "1") (pinfunction "1_1") (pintype "passive"))
      (node (ref "UAI") (pin "4") (pinfunction "Y1_4") (pintype "passive"))
    )
    (net (code "157") (name "Net-(UL1-IN+)") (class "Default")
      (node (ref "CL1") (pin "1") (pinfunction "1_1") (pintype "passive"))
      (node (ref "RL1") (pin "1") (pinfunction "1_1") (pintype "passive"))
      (node (ref "UL1") (pin "3") (pinfunction "IN+_3") (pintype "passive"))
    )
    (net (code "158") (name "Net-(UL1-IN-)") (class "Default")
      (node (ref "CL4") (pin "1") (pinfunction "1_1") (pintype "passive"))
      (node (ref "RL4") (pin "2") (pinfunction "2_2") (pintype "passive"))
      (node (ref "RL5") (pin "2") (pinfunction "2_2") (pintype "passive"))
      (node (ref "UL1") (pin "4") (pinfunction "IN-_4") (pintype "passive"))
    )
    (net (code "159") (name "Net-(UL2A-IN+)") (class "Default")
      (node (ref "CL7") (pin "1") (pinfunction "1_1") (pintype "passive"))
      (node (ref "CL8") (pin "2") (pinfunction "2_2") (pintype "passive"))
      (node (ref "RL7") (pin "1") (pinfunction "1_1") (pintype "passive"))
      (node (ref "RL8") (pin "2") (pinfunction "2_2") (pintype "passive"))
      (node (ref "UL2") (pin "3") (pinfunction "IN+_3") (pintype "passive"))
      (node (ref "UL2") (pin "5") (pinfunction "IN+_5") (pintype "passive"))
    )
    (net (code "160") (name "Net-(UL3A-IN+)") (class "Default")
      (node (ref "CLE") (pin "1") (pinfunction "1_1") (pintype "passive"))
      (node (ref "RLK") (pin "1") (pinfunction "1_1") (pintype "passive"))
      (node (ref "UL3") (pin "3") (pinfunction "IN+_3") (pintype "passive"))
    )
    (net (code "161") (name "Net-(UL3A-IN-)") (class "Default")
      (node (ref "CLD") (pin "1") (pinfunction "1_1") (pintype "passive"))
      (node (ref "RLJ") (pin "1") (pinfunction "1_1") (pintype "passive"))
      (node (ref "UL3") (pin "2") (pinfunction "IN-_2") (pintype "passive"))
    )
    (net (code "162") (name "Net-(UL3B-IN+)") (class "Default")
      (node (ref "CLJ") (pin "1") (pinfunction "1_1") (pintype "passive"))
      (node (ref "RLU") (pin "1") (pinfunction "1_1") (pintype "passive"))
      (node (ref "UL3") (pin "5") (pinfunction "IN+_5") (pintype "passive"))
    )
    (net (code "163") (name "Net-(UL3B-IN-)") (class "Default")
      (node (ref "CLI") (pin "1") (pinfunction "1_1") (pintype "passive"))
      (node (ref "RLT") (pin "1") (pinfunction "1_1") (pintype "passive"))
      (node (ref "UL3") (pin "6") (pinfunction "IN-_6") (pintype "passive"))
    )
    (net (code "164") (name "Net-(UR1-IN+)") (class "Default")
      (node (ref "CR1") (pin "1") (pinfunction "1_1") (pintype "passive"))
      (node (ref "RR1") (pin "1") (pinfunction "1_1") (pintype "passive"))
      (node (ref "UR1") (pin "3") (pinfunction "IN+_3") (pintype "passive"))
    )
    (net (code "165") (name "Net-(UR1-IN-)") (class "Default")
      (node (ref "CR4") (pin "1") (pinfunction "1_1") (pintype "passive"))
      (node (ref "RR4") (pin "2") (pinfunction "2_2") (pintype "passive"))
      (node (ref "RR5") (pin "2") (pinfunction "2_2") (pintype "passive"))
      (node (ref "UR1") (pin "4") (pinfunction "IN-_4") (pintype "passive"))
    )
    (net (code "166") (name "Net-(UR2A-IN+)") (class "Default")
      (node (ref "CR7") (pin "1") (pinfunction "1_1") (pintype "passive"))
      (node (ref "CR8") (pin "2") (pinfunction "2_2") (pintype "passive"))
      (node (ref "RR7") (pin "1") (pinfunction "1_1") (pintype "passive"))
      (node (ref "RR8") (pin "2") (pinfunction "2_2") (pintype "passive"))
      (node (ref "UR2") (pin "3") (pinfunction "IN+_3") (pintype "passive"))
      (node (ref "UR2") (pin "5") (pinfunction "IN+_5") (pintype "passive"))
    )
    (net (code "167") (name "Net-(UR3A-IN+)") (class "Default")
      (node (ref "CRE") (pin "1") (pinfunction "1_1") (pintype "passive"))
      (node (ref "RRK") (pin "1") (pinfunction "1_1") (pintype "passive"))
      (node (ref "UR3") (pin "3") (pinfunction "IN+_3") (pintype "passive"))
    )
    (net (code "168") (name "Net-(UR3A-IN-)") (class "Default")
      (node (ref "CRD") (pin "1") (pinfunction "1_1") (pintype "passive"))
      (node (ref "RRJ") (pin "1") (pinfunction "1_1") (pintype "passive"))
      (node (ref "UR3") (pin "2") (pinfunction "IN-_2") (pintype "passive"))
    )
    (net (code "169") (name "Net-(UR3B-IN+)") (class "Default")
      (node (ref "CRJ") (pin "1") (pinfunction "1_1") (pintype "passive"))
      (node (ref "RRU") (pin "1") (pinfunction "1_1") (pintype "passive"))
      (node (ref "UR3") (pin "5") (pinfunction "IN+_5") (pintype "passive"))
    )
    (net (code "170") (name "Net-(UR3B-IN-)") (class "Default")
      (node (ref "CRI") (pin "1") (pinfunction "1_1") (pintype "passive"))
      (node (ref "RRT") (pin "1") (pinfunction "1_1") (pintype "passive"))
      (node (ref "UR3") (pin "6") (pinfunction "IN-_6") (pintype "passive"))
    )
  )
)
